# ProPrj_M-power_2025-07-02.net
KiCad netlist of a schematic drawn in EasyEDA Pro
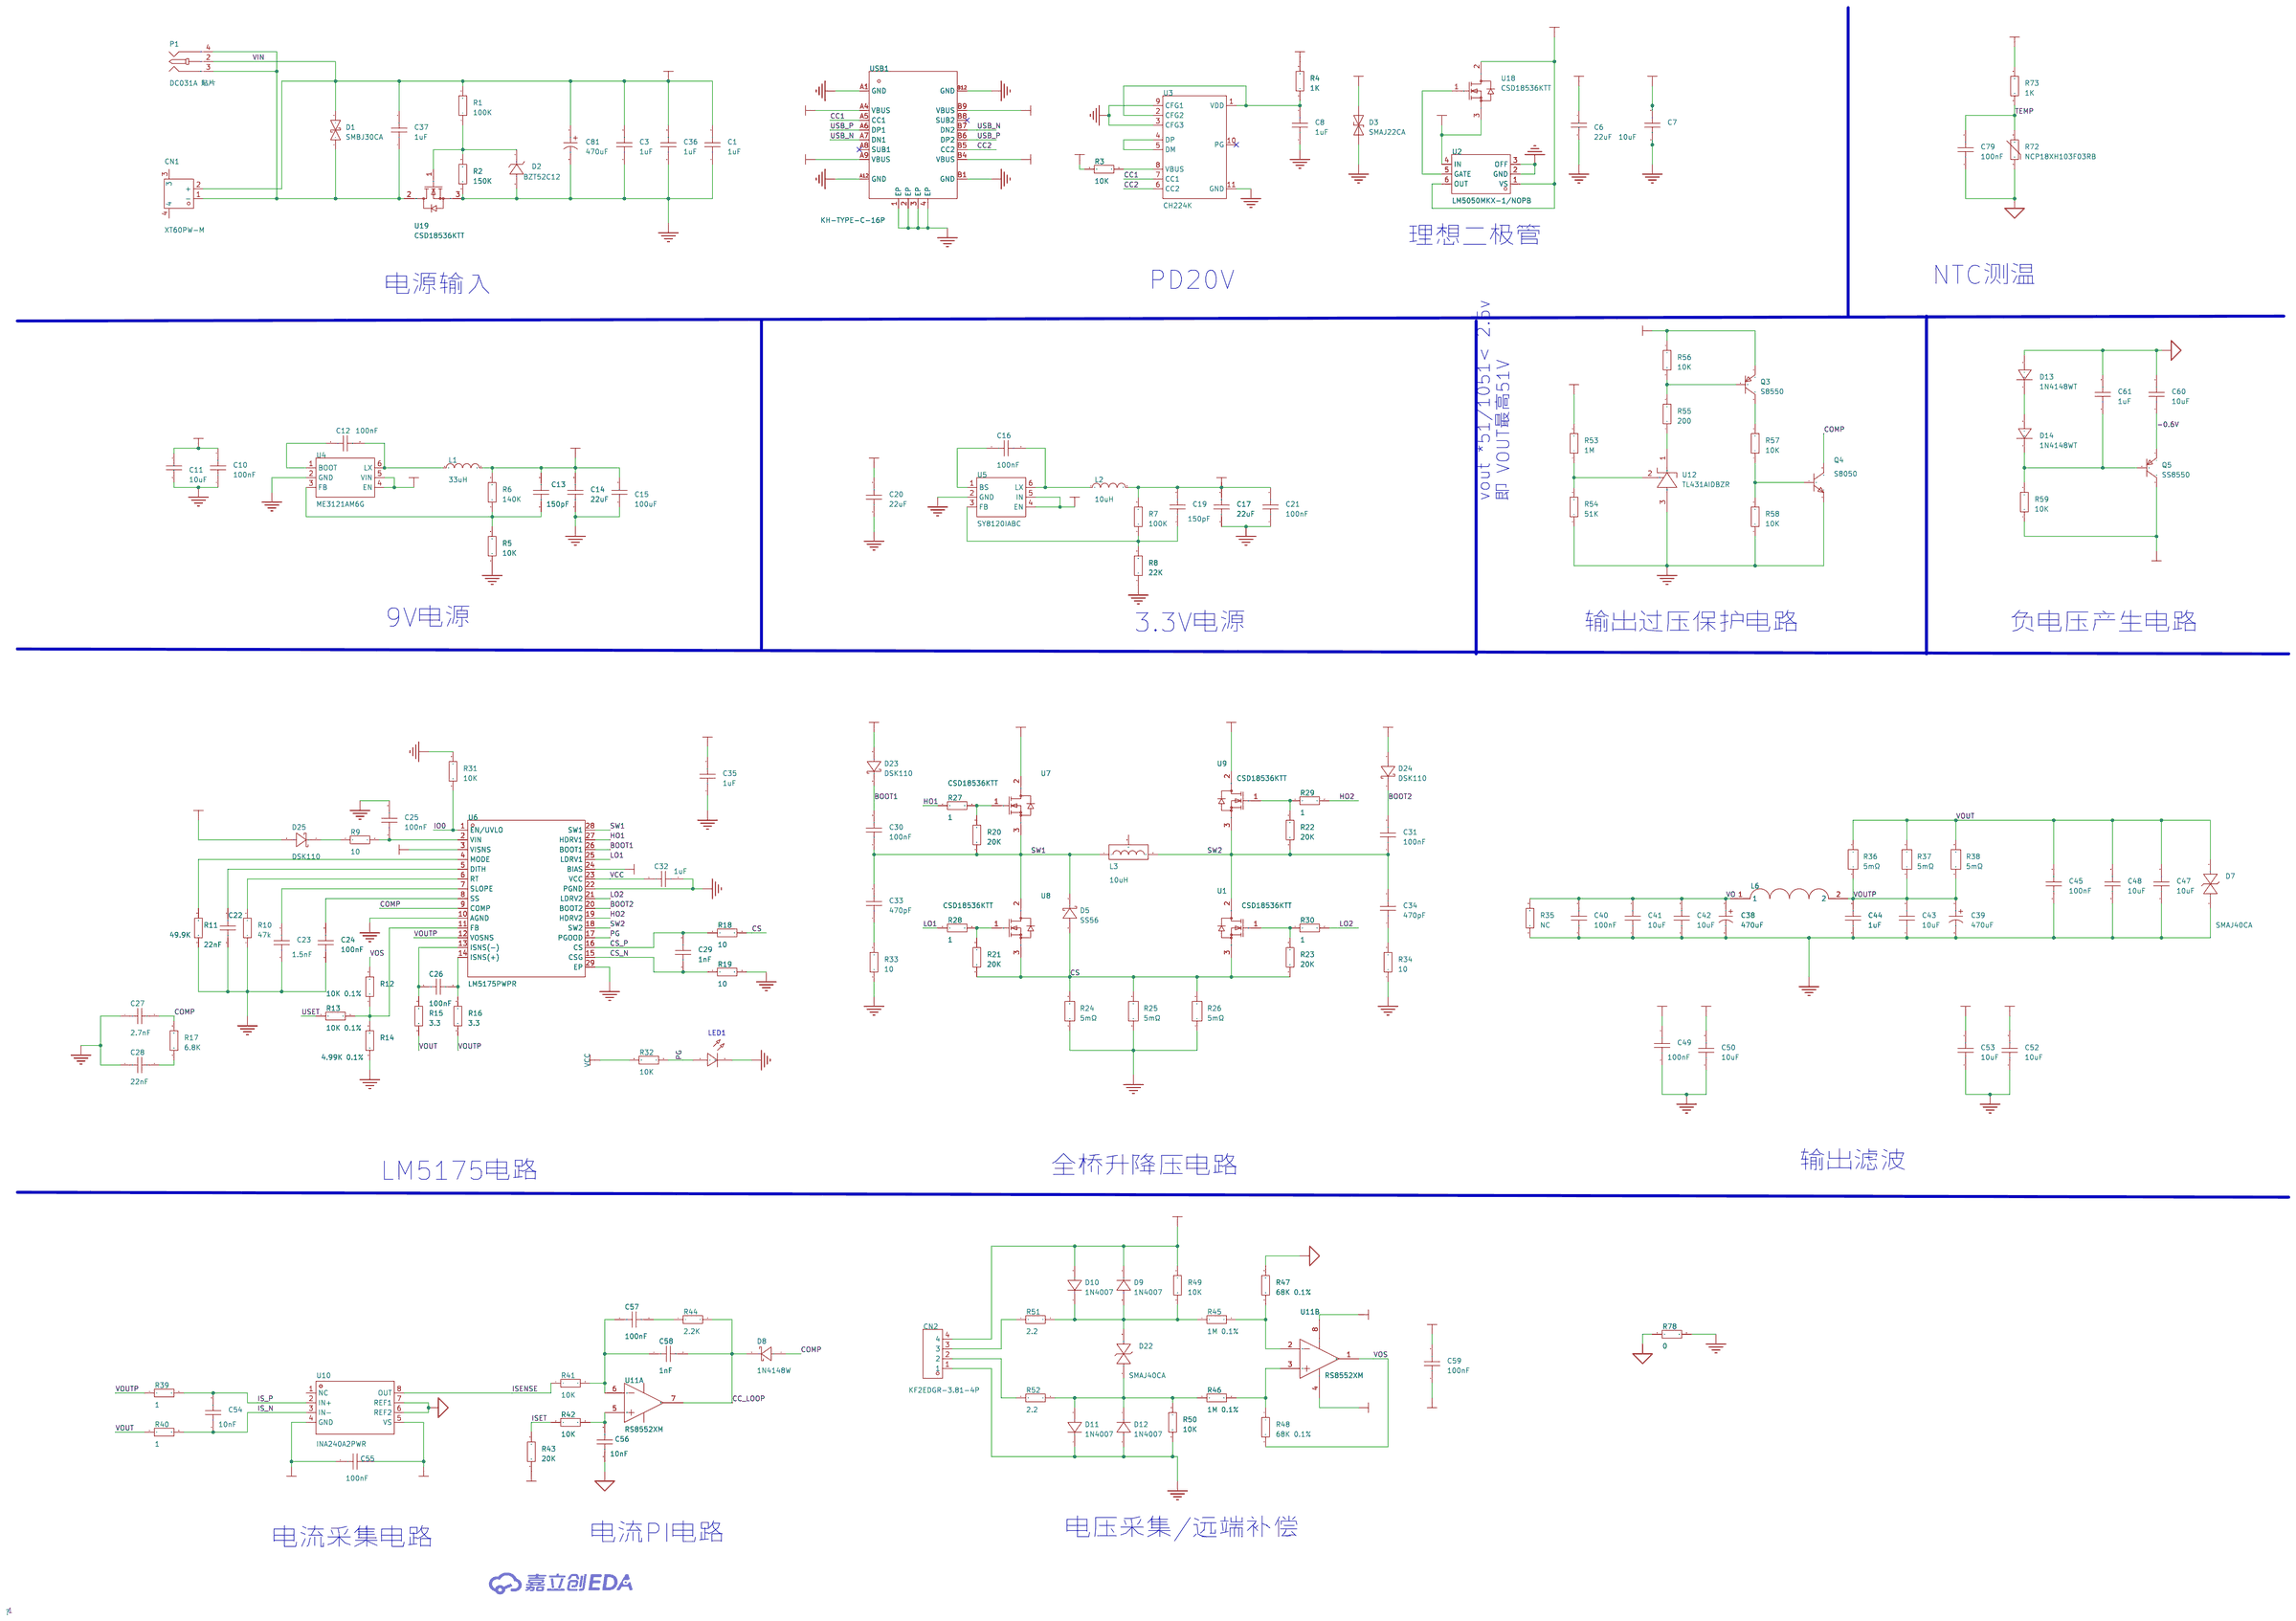
[diagram p0: 功率]
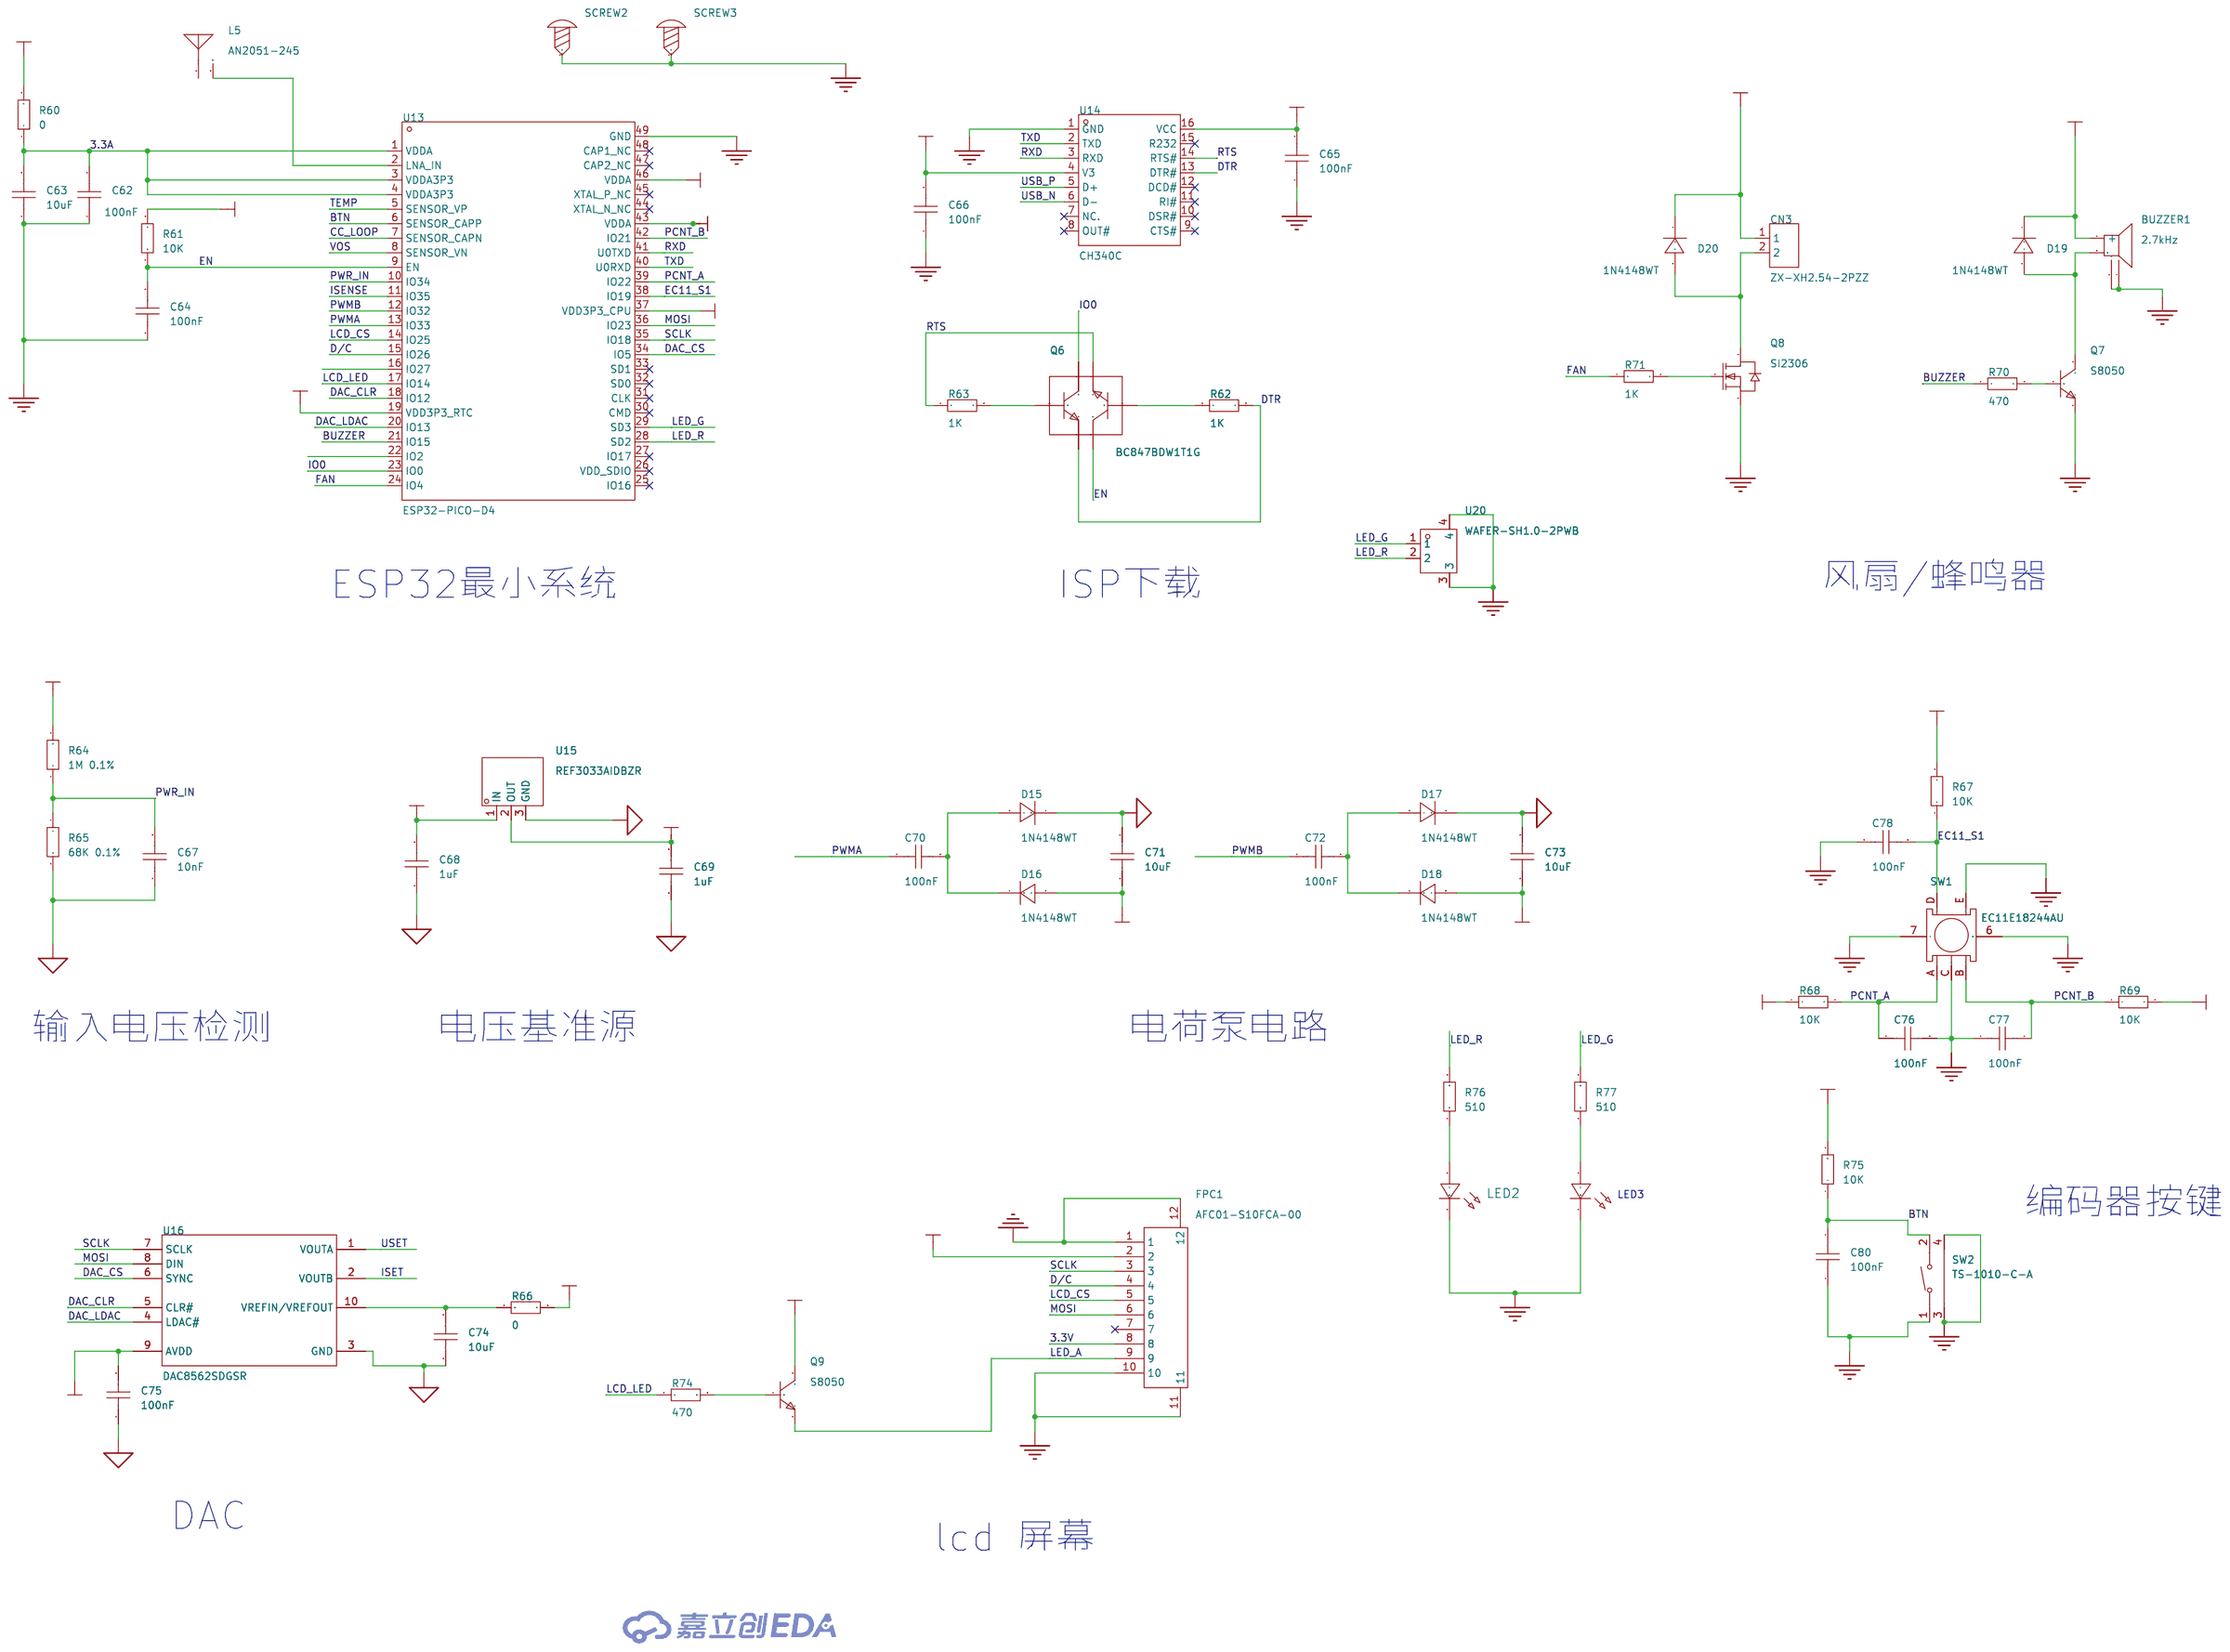
[diagram p1: 控制]

(export (version "E")
  (design (tool "Eeschema 10.0.6"))
  (components
    (comp (ref "C1")
      (value "1uF")
      (footprint "easyedapro:C0603")
      (fields
        (field (name "Manufacturer Part") "CL31B105KBHNNNE")
        (field (name "Manufacturer") "SAMSUNG(三星)")
      )
      (libsource (lib "easyedapro") (part "CapAcitance"))
    )
    (comp (ref "C3")
      (value "1uF")
      (footprint "easyedapro:C0603")
      (fields
        (field (name "Manufacturer Part") "CL31B105KBHNNNE")
        (field (name "Manufacturer") "SAMSUNG(三星)")
      )
      (libsource (lib "easyedapro") (part "CapAcitance"))
    )
    (comp (ref "C6")
      (value "22uF")
      (footprint "easyedapro:C1206")
      (description "容值:22uF;精度:±10%;额定电压:25V;材质(温度系数):X5R;")
      (fields
        (field (name "Manufacturer Part") "CL31A226KAHNNNE")
        (field (name "Manufacturer") "SAMSUNG(三星)")
      )
      (libsource (lib "easyedapro") (part "CL31A226KAHNNNE"))
    )
    (comp (ref "C7")
      (value "10uF")
      (footprint "easyedapro:C0603")
      (description "容值:10uF;精度:±20%;额定电压:25V;材质(温度系数):X5R;")
      (fields
        (field (name "Manufacturer Part") "CL10A106MA8NRNC")
        (field (name "Manufacturer") "SAMSUNG(三星)")
      )
      (libsource (lib "easyedapro") (part "CL10A106MA8NRNC"))
    )
    (comp (ref "C8")
      (value "1uF")
      (footprint "easyedapro:C0603")
      (libsource (lib "easyedapro") (part "CapAcitance"))
    )
    (comp (ref "C10")
      (value "100nF")
      (footprint "easyedapro:C0603")
      (libsource (lib "easyedapro") (part "CapAcitance"))
    )
    (comp (ref "C11")
      (value "10uF")
      (footprint "easyedapro:C1206")
      (description "容值:10uF;精度:±10%;额定电压:50V;材质(温度系数):X5R;")
      (fields
        (field (name "Manufacturer Part") "CL31A106KBHNNNE")
        (field (name "Manufacturer") "SAMSUNG(三星)")
      )
      (libsource (lib "easyedapro") (part "CL31A106KBHNNNE"))
    )
    (comp (ref "C12")
      (value "100nF")
      (footprint "easyedapro:C0603")
      (libsource (lib "easyedapro") (part "CapAcitance"))
    )
    (comp (ref "C13")
      (value "150pF")
      (footprint "easyedapro:C0603")
      (libsource (lib "easyedapro") (part "CapAcitance"))
    )
    (comp (ref "C14")
      (value "22uF")
      (footprint "easyedapro:C0805")
      (description "容值:22uF;精度:±20%;额定电压:25V;材质(温度系数):X5R;")
      (fields
        (field (name "Manufacturer Part") "CL21A226MAYNNNE")
        (field (name "Manufacturer") "SAMSUNG(三星)")
      )
      (libsource (lib "easyedapro") (part "CL21A226MAYNNNE"))
    )
    (comp (ref "C15")
      (value "100uF")
      (footprint "easyedapro:C1206")
      (description "容值:100uF;精度:±20%;额定电压:6.3V;材质(温度系数):X5R;")
      (fields
        (field (name "Manufacturer Part") "CL31A107MQHNNNE")
        (field (name "Manufacturer") "SAMSUNG(三星)")
      )
      (libsource (lib "easyedapro") (part "CL31A107MQHNNNE"))
    )
    (comp (ref "C16")
      (value "100nF")
      (footprint "easyedapro:C0603")
      (libsource (lib "easyedapro") (part "CapAcitance"))
    )
    (comp (ref "C17")
      (value "22uF")
      (footprint "easyedapro:C0603")
      (description "容值:22uF;精度:±20%;额定电压:6.3V;材质(温度系数):X5R;")
      (fields
        (field (name "Manufacturer Part") "CL10A226MQ8NRNC")
        (field (name "Manufacturer") "SAMSUNG(三星)")
      )
      (libsource (lib "easyedapro") (part "CL10A226MQ8NRNC"))
    )
    (comp (ref "C19")
      (value "150pF")
      (footprint "easyedapro:C0603")
      (libsource (lib "easyedapro") (part "CapAcitance"))
    )
    (comp (ref "C20")
      (value "22uF")
      (footprint "easyedapro:C0603")
      (description "容值:22uF;精度:±20%;额定电压:6.3V;材质(温度系数):X5R;")
      (fields
        (field (name "Manufacturer Part") "CL10A226MQ8NRNC")
        (field (name "Manufacturer") "SAMSUNG(三星)")
      )
      (libsource (lib "easyedapro") (part "CL10A226MQ8NRNC"))
    )
    (comp (ref "C21")
      (value "100nF")
      (footprint "easyedapro:C0603")
      (libsource (lib "easyedapro") (part "CapAcitance"))
    )
    (comp (ref "C22")
      (value "22nF")
      (footprint "easyedapro:C0603")
      (libsource (lib "easyedapro") (part "CapAcitance"))
    )
    (comp (ref "C23")
      (value "1.5nF")
      (footprint "easyedapro:C0603")
      (libsource (lib "easyedapro") (part "CapAcitance"))
    )
    (comp (ref "C24")
      (value "100nF")
      (footprint "easyedapro:C0603")
      (libsource (lib "easyedapro") (part "CapAcitance"))
    )
    (comp (ref "C25")
      (value "100nF")
      (footprint "easyedapro:C0603")
      (libsource (lib "easyedapro") (part "CapAcitance"))
    )
    (comp (ref "C26")
      (value "100nF")
      (footprint "easyedapro:C0603")
      (libsource (lib "easyedapro") (part "CapAcitance"))
    )
    (comp (ref "C27")
      (value "2.7nF")
      (footprint "easyedapro:C0603")
      (libsource (lib "easyedapro") (part "CapAcitance"))
    )
    (comp (ref "C28")
      (value "22nF")
      (footprint "easyedapro:C0603")
      (libsource (lib "easyedapro") (part "CapAcitance"))
    )
    (comp (ref "C29")
      (value "1nF")
      (footprint "easyedapro:C0603")
      (libsource (lib "easyedapro") (part "CapAcitance"))
    )
    (comp (ref "C30")
      (value "100nF")
      (footprint "easyedapro:C0603")
      (libsource (lib "easyedapro") (part "CapAcitance"))
    )
    (comp (ref "C31")
      (value "100nF")
      (footprint "easyedapro:C0603")
      (libsource (lib "easyedapro") (part "CapAcitance"))
    )
    (comp (ref "C32")
      (value "1uF")
      (footprint "easyedapro:C0603")
      (libsource (lib "easyedapro") (part "CapAcitance"))
    )
    (comp (ref "C33")
      (value "470pF")
      (footprint "easyedapro:C0603")
      (libsource (lib "easyedapro") (part "CapAcitance"))
    )
    (comp (ref "C34")
      (value "470pF")
      (footprint "easyedapro:C0603")
      (libsource (lib "easyedapro") (part "CapAcitance"))
    )
    (comp (ref "C35")
      (value "1uF")
      (footprint "easyedapro:C0603")
      (libsource (lib "easyedapro") (part "CapAcitance"))
    )
    (comp (ref "C36")
      (value "1uF")
      (footprint "easyedapro:C0603")
      (fields
        (field (name "Manufacturer Part") "CL31B105KBHNNNE")
        (field (name "Manufacturer") "SAMSUNG(三星)")
      )
      (libsource (lib "easyedapro") (part "CapAcitance"))
    )
    (comp (ref "C37")
      (value "1uF")
      (footprint "easyedapro:C0603")
      (fields
        (field (name "Manufacturer Part") "CL31B105KBHNNNE")
        (field (name "Manufacturer") "SAMSUNG(三星)")
      )
      (libsource (lib "easyedapro") (part "CapAcitance"))
    )
    (comp (ref "C38")
      (value "470uF")
      (footprint "easyedapro:CAP-TH_BD10.0-P5.00-D0.6-FD-A")
      (description "容值:470uF;精度:±20%;额定电压:50V;纹波电流:4.1A@100Hz;等效串联电阻(ESR):18mΩ@100kHz;类型:-;")
      (fields (field (name "Manufacturer Part") "PA50V470M10x17") (field (name "Manufacturer") "捷而瑞"))
      (libsource (lib "easyedapro") (part "PA50V470M10X17"))
    )
    (comp (ref "C39")
      (value "470uF")
      (footprint "easyedapro:CAP-TH_BD10.0-P5.00-D0.6-FD-A")
      (description "容值:470uF;精度:±20%;额定电压:50V;纹波电流:4.1A@100Hz;等效串联电阻(ESR):18mΩ@100kHz;类型:-;")
      (fields (field (name "Manufacturer Part") "PA50V470M10x17") (field (name "Manufacturer") "捷而瑞"))
      (libsource (lib "easyedapro") (part "PA50V470M10X17"))
    )
    (comp (ref "C40")
      (value "100nF")
      (footprint "easyedapro:C0603")
      (libsource (lib "easyedapro") (part "CapAcitance"))
    )
    (comp (ref "C41")
      (value "10uF")
      (footprint "easyedapro:C0603")
      (fields
        (field (name "Manufacturer Part") "CL31B105KBHNNNE")
        (field (name "Manufacturer") "SAMSUNG(三星)")
      )
      (libsource (lib "easyedapro") (part "CapAcitance"))
    )
    (comp (ref "C42")
      (value "10uF")
      (footprint "easyedapro:C0603")
      (fields
        (field (name "Manufacturer Part") "CL31B105KBHNNNE")
        (field (name "Manufacturer") "SAMSUNG(三星)")
      )
      (libsource (lib "easyedapro") (part "CapAcitance"))
    )
    (comp (ref "C43")
      (value "10uF")
      (footprint "easyedapro:C0603")
      (fields
        (field (name "Manufacturer Part") "CL31B105KBHNNNE")
        (field (name "Manufacturer") "SAMSUNG(三星)")
      )
      (libsource (lib "easyedapro") (part "CapAcitance"))
    )
    (comp (ref "C44")
      (value "1uF")
      (footprint "easyedapro:C0603")
      (fields
        (field (name "Manufacturer Part") "CL31B105KBHNNNE")
        (field (name "Manufacturer") "SAMSUNG(三星)")
      )
      (libsource (lib "easyedapro") (part "CapAcitance"))
    )
    (comp (ref "C45")
      (value "100nF")
      (footprint "easyedapro:C0603")
      (libsource (lib "easyedapro") (part "CapAcitance"))
    )
    (comp (ref "C47")
      (value "10uF")
      (footprint "easyedapro:C0603")
      (fields
        (field (name "Manufacturer Part") "CL31B105KBHNNNE")
        (field (name "Manufacturer") "SAMSUNG(三星)")
      )
      (libsource (lib "easyedapro") (part "CapAcitance"))
    )
    (comp (ref "C48")
      (value "10uF")
      (footprint "easyedapro:C0603")
      (fields
        (field (name "Manufacturer Part") "CL31B105KBHNNNE")
        (field (name "Manufacturer") "SAMSUNG(三星)")
      )
      (libsource (lib "easyedapro") (part "CapAcitance"))
    )
    (comp (ref "C49")
      (value "100nF")
      (footprint "easyedapro:C0603")
      (libsource (lib "easyedapro") (part "CapAcitance"))
    )
    (comp (ref "C50")
      (value "10uF")
      (footprint "easyedapro:C0603")
      (fields
        (field (name "Manufacturer Part") "CL31B105KBHNNNE")
        (field (name "Manufacturer") "SAMSUNG(三星)")
      )
      (libsource (lib "easyedapro") (part "CapAcitance"))
    )
    (comp (ref "C52")
      (value "10uF")
      (footprint "easyedapro:C0603")
      (fields
        (field (name "Manufacturer Part") "CL31B105KBHNNNE")
        (field (name "Manufacturer") "SAMSUNG(三星)")
      )
      (libsource (lib "easyedapro") (part "CapAcitance"))
    )
    (comp (ref "C53")
      (value "10uF")
      (footprint "easyedapro:C0603")
      (fields
        (field (name "Manufacturer Part") "CL31B105KBHNNNE")
        (field (name "Manufacturer") "SAMSUNG(三星)")
      )
      (libsource (lib "easyedapro") (part "CapAcitance"))
    )
    (comp (ref "C54")
      (value "10nF")
      (footprint "easyedapro:C0603")
      (libsource (lib "easyedapro") (part "CapAcitance"))
    )
    (comp (ref "C55")
      (value "100nF")
      (footprint "easyedapro:C0603")
      (libsource (lib "easyedapro") (part "CapAcitance"))
    )
    (comp (ref "C56")
      (value "10nF")
      (footprint "easyedapro:C0603")
      (libsource (lib "easyedapro") (part "CapAcitance"))
    )
    (comp (ref "C57")
      (value "100nF")
      (footprint "easyedapro:C0603")
      (libsource (lib "easyedapro") (part "CapAcitance"))
    )
    (comp (ref "C58")
      (value "1nF")
      (footprint "easyedapro:C0603")
      (libsource (lib "easyedapro") (part "CapAcitance"))
    )
    (comp (ref "C59")
      (value "100nF")
      (footprint "easyedapro:C0603")
      (libsource (lib "easyedapro") (part "CapAcitance"))
    )
    (comp (ref "C60")
      (value "10uF")
      (footprint "easyedapro:C0603")
      (libsource (lib "easyedapro") (part "CapAcitance"))
    )
    (comp (ref "C61")
      (value "1uF")
      (footprint "easyedapro:C0603")
      (libsource (lib "easyedapro") (part "CapAcitance"))
    )
    (comp (ref "C79")
      (value "100nF")
      (footprint "easyedapro:C0603")
      (libsource (lib "easyedapro") (part "CapAcitance"))
    )
    (comp (ref "C81")
      (value "470uF")
      (footprint "easyedapro:CAP-TH_BD10.0-P5.00-D0.6-FD-A")
      (description "容值:470uF;精度:±20%;额定电压:50V;纹波电流:4.1A@100Hz;等效串联电阻(ESR):18mΩ@100kHz;类型:-;")
      (fields (field (name "Manufacturer Part") "PA50V470M10x17") (field (name "Manufacturer") "捷而瑞"))
      (libsource (lib "easyedapro") (part "PA50V470M10X17"))
    )
    (comp (ref "CN1")
      (value "XT60PW-M")
      (footprint "easyedapro:CONN-TH_XT60PW-M")
      (description "类别:-;类型1:-;")
      (fields (field (name "Manufacturer") "AMASS(艾迈斯)"))
      (libsource (lib "easyedapro") (part "XT60PW-M"))
    )
    (comp (ref "CN2")
      (value "KF2EDGR-3.81-4P")
      (footprint "easyedapro:CONN-TH_4P-P3.81_KF2EDGR-3.81-4P")
      (fields (field (name "Manufacturer") "KEFA(科发)"))
      (libsource (lib "easyedapro") (part "KF2EDGR-3.81-4P"))
    )
    (comp (ref "D1")
      (value "SMBJ30CA")
      (footprint "easyedapro:SMB_L4.6-W3.6-LS5.3-BI")
      (description "反向截止电压(Vrwm):30V;最大钳位电压:48.4V;峰值脉冲电流(Ipp)@10/1000us:12.4A;击穿电压:33.3V;")
      (fields (field (name "Manufacturer") "MDD"))
      (libsource (lib "easyedapro") (part "SMBJ30CA_C113999"))
    )
    (comp (ref "D2")
      (value "BZT52C12")
      (footprint "easyedapro:SOD-123_L2.7-W1.6-LS3.7-RD")
      (description "二极管配置:独立式;稳压值(标称值):12V;稳压值(范围):11.4V~12.6V;功率(Pd):500mW;")
      (fields (field (name "Manufacturer") "宏迦橙"))
      (libsource (lib "easyedapro") (part "BZT52C12_C19077410"))
    )
    (comp (ref "D3")
      (value "SMAJ22CA")
      (footprint "easyedapro:SMA_L4.4-W2.6-LS5.0-BI")
      (description "反向截止电压(Vrwm):22V;最大钳位电压:35.5V;峰值脉冲电流(Ipp):11.3A;峰值脉冲功率(Ppp):400W;击穿电压:24.4V;")
      (fields (field (name "Manufacturer") "Littelfuse(美国力特)"))
      (libsource (lib "easyedapro") (part "SMAJ22CA"))
    )
    (comp (ref "D5")
      (value "SS56")
      (footprint "easyedapro:SMA_L4.3-W2.6-LS5.0-RD")
      (description "二极管配置:独立式;正向压降(Vf):700mV@5.0A;直流反向耐压(Vr):60V;整流电流:5A;")
      (fields (field (name "Manufacturer") "宏迦橙"))
      (libsource (lib "easyedapro") (part "SS56_C18199169"))
    )
    (comp (ref "D7")
      (value "SMAJ40CA")
      (footprint "easyedapro:SMA_L4.3-W2.6-LS5.0-BI")
      (description "极性:双向;反向截止电压(Vrwm):40V;钳位电压:64.5V;峰值脉冲电流(Ipp):6.2A;峰值脉冲功率(Ppp):400W;击穿电压:44.4V;")
      (fields (field (name "Manufacturer") "宏嘉诚"))
      (libsource (lib "easyedapro") (part "SMAJ40CA_C19077552"))
    )
    (comp (ref "D8")
      (value "1N4148W")
      (footprint "easyedapro:SOD-123_L2.7-W1.6-LS3.7-FD")
      (description "二极管配置:独立式;正向压降(Vf):1.25V@150mA;直流反向耐压(Vr):100V;整流电流:150mA;反向恢复时间(trr):4ns;")
      (fields (field (name "Manufacturer") "宏迦橙"))
      (libsource (lib "easyedapro") (part "1N4148W_C7420318"))
    )
    (comp (ref "D9")
      (value "1N4007")
      (footprint "easyedapro:SMA_L4.3-W2.5-LS5.0-RD")
      (description "二极管配置:独立式;正向压降(Vf):1.1V@1A;直流反向耐压(Vr):1kV;整流电流:1A;")
      (fields (field (name "Manufacturer") "TWGMC(台湾迪嘉)"))
      (libsource (lib "easyedapro") (part "1N4007_C727081"))
    )
    (comp (ref "D10")
      (value "1N4007")
      (footprint "easyedapro:SMA_L4.3-W2.5-LS5.0-RD")
      (description "二极管配置:独立式;正向压降(Vf):1.1V@1A;直流反向耐压(Vr):1kV;整流电流:1A;")
      (fields (field (name "Manufacturer") "TWGMC(台湾迪嘉)"))
      (libsource (lib "easyedapro") (part "1N4007_C727081"))
    )
    (comp (ref "D11")
      (value "1N4007")
      (footprint "easyedapro:SMA_L4.3-W2.5-LS5.0-RD")
      (description "二极管配置:独立式;正向压降(Vf):1.1V@1A;直流反向耐压(Vr):1kV;整流电流:1A;")
      (fields (field (name "Manufacturer") "TWGMC(台湾迪嘉)"))
      (libsource (lib "easyedapro") (part "1N4007_C727081"))
    )
    (comp (ref "D12")
      (value "1N4007")
      (footprint "easyedapro:SMA_L4.3-W2.5-LS5.0-RD")
      (description "二极管配置:独立式;正向压降(Vf):1.1V@1A;直流反向耐压(Vr):1kV;整流电流:1A;")
      (fields (field (name "Manufacturer") "TWGMC(台湾迪嘉)"))
      (libsource (lib "easyedapro") (part "1N4007_C727081"))
    )
    (comp (ref "D13")
      (value "1N4148WT")
      (footprint "easyedapro:SOD-523_L1.2-W0.8-LS1.6-RD")
      (description "二极管配置:独立式;正向压降(Vf):1V@10mA;直流反向耐压(Vr):75V;整流电流:300mA;反向恢复时间(trr):4ns;")
      (fields (field (name "Manufacturer") "onsemi(安森美)"))
      (libsource (lib "easyedapro") (part "1N4148WT_C232841"))
    )
    (comp (ref "D14")
      (value "1N4148WT")
      (footprint "easyedapro:SOD-523_L1.2-W0.8-LS1.6-RD")
      (description "二极管配置:独立式;正向压降(Vf):1V@10mA;直流反向耐压(Vr):75V;整流电流:300mA;反向恢复时间(trr):4ns;")
      (fields (field (name "Manufacturer") "onsemi(安森美)"))
      (libsource (lib "easyedapro") (part "1N4148WT_C232841"))
    )
    (comp (ref "D22")
      (value "SMAJ40CA")
      (footprint "easyedapro:SMA_L4.3-W2.6-LS5.0-BI")
      (description "极性:双向;反向截止电压(Vrwm):40V;钳位电压:64.5V;峰值脉冲电流(Ipp):6.2A;峰值脉冲功率(Ppp):400W;击穿电压:44.4V;")
      (fields (field (name "Manufacturer") "宏嘉诚"))
      (libsource (lib "easyedapro") (part "SMAJ40CA_C19077552"))
    )
    (comp (ref "D23")
      (value "DSK110")
      (footprint "easyedapro:SOD-123FL_L2.8-W1.9-LS3.7-RD")
      (description "二极管配置:独立式;正向压降(Vf):850mV@1A;直流反向耐压(Vr):100V;整流电流:1A;")
      (fields (field (name "Manufacturer") "宏迦橙"))
      (libsource (lib "easyedapro") (part "DSK110_C22466354"))
    )
    (comp (ref "D24")
      (value "DSK110")
      (footprint "easyedapro:SOD-123FL_L2.8-W1.9-LS3.7-RD")
      (description "二极管配置:独立式;正向压降(Vf):850mV@1A;直流反向耐压(Vr):100V;整流电流:1A;")
      (fields (field (name "Manufacturer") "宏迦橙"))
      (libsource (lib "easyedapro") (part "DSK110_C22466354"))
    )
    (comp (ref "D25")
      (value "DSK110")
      (footprint "easyedapro:SOD-123FL_L2.8-W1.9-LS3.7-RD")
      (description "二极管配置:独立式;正向压降(Vf):850mV@1A;直流反向耐压(Vr):100V;整流电流:1A;")
      (fields (field (name "Manufacturer") "宏迦橙"))
      (libsource (lib "easyedapro") (part "DSK110_C22466354"))
    )
    (comp (ref "L1")
      (value "33uH")
      (footprint "easyedapro:IND-SMD_L7.0-W6.6_FXL0630")
      (description "电感值:33uH;精度:±20%;额定电流:2A;饱和电流(Isat):2.5A;类型:一体成型电感;")
      (fields (field (name "Manufacturer Part") "FXL0630-330-M") (field (name "Manufacturer") "cjiang(长江微电)"))
      (libsource (lib "easyedapro") (part "FXL0630-330-M"))
    )
    (comp (ref "L2")
      (value "10uH")
      (footprint "easyedapro:IND-SMD_L7.3-W6.8")
      (description "电感值:10uH;精度:±20%;额定电流:4.5A;饱和电流(Isat):5.5A;类型:一体成型电感;")
      (fields (field (name "Manufacturer Part") "FXL0630-100-M") (field (name "Manufacturer") "cjiang(长江微电)"))
      (libsource (lib "easyedapro") (part "FXL0630-100-M"))
    )
    (comp (ref "L3")
      (value "10uH")
      (footprint "easyedapro:IND-SMD_3P-L28.0-W19.4_7443641000B")
      (description "电感值:10uH;精度:±20%;额定电流:30A;饱和电流(Isat):31A;类型:扁平线大电流电感;")
      (fields (field (name "Manufacturer Part") "MTP2918S-100M") (field (name "Manufacturer") "COILMX(迈翔科技)"))
      (libsource (lib "easyedapro") (part "MTP2918S-100M"))
    )
    (comp (ref "L6") (value "~") (libsource (lib "easyedapro") (part "磁棒电感1.5uh")))
    (comp (ref "LED1")
      (value "~")
      (footprint "easyedapro:LED_0603")
      (libsource (lib "easyedapro") (part "LED_G"))
    )
    (comp (ref "P1")
      (value "DC031A 贴片")
      (footprint "easyedapro:DC-IN-SMD_DC031A")
      (description "连接器类型:DC电源插座;安装方式:卧贴;触点内径:1.3mm;触点外径:3.7mm;额定电流:-;额定电压:-;工作温度范围:-;")
      (fields (field (name "Manufacturer") "BOOMELE(博穆精密)"))
      (libsource (lib "easyedapro") (part "DC031A DCseat"))
    )
    (comp (ref "Q3")
      (value "S8550")
      (footprint "easyedapro:SOT-23-3_L2.9-W1.3-P1.90-LS2.4-BR")
      (description "晶体管类型:PNP;集电极电流(Ic):500mA;集射极击穿电压(Vceo):25V;耗散功率(Pd):300mW;直流电流增益(hFE):120@500mA,1.0V;")
      (fields (field (name "Manufacturer") "宏嘉诚"))
      (libsource (lib "easyedapro") (part "S8550_C20069126"))
    )
    (comp (ref "Q4")
      (value "S8050")
      (footprint "easyedapro:SOT-23-3_L2.9-W1.3-P1.90-LS2.3-BR")
      (description "晶体管类型:NPN;集电极电流(Ic):500mA;集射极击穿电压(Vceo):25V;耗散功率(Pd):300mW;直流电流增益(hFE):120@50mA,1.0V;")
      (fields (field (name "Manufacturer") "宏嘉诚"))
      (libsource (lib "easyedapro") (part "S8050_C20069125"))
    )
    (comp (ref "Q5")
      (value "SS8550")
      (footprint "easyedapro:SOT-23-3_L2.9-W1.3-P1.90-LS2.4-BR")
      (description "晶体管类型:PNP;集电极电流(Ic):1.5A;集射极击穿电压(Vceo):25V;耗散功率(Pd):300mW;直流电流增益(hFE):120@100mA,1.0V;")
      (fields (field (name "Manufacturer") "宏嘉诚"))
      (libsource (lib "easyedapro") (part "SS8550_C7420371"))
    )
    (comp (ref "R1") (value "100K") (footprint "easyedapro:R0603") (libsource (lib "easyedapro") (part "电阻")))
    (comp (ref "R2") (value "150K") (footprint "easyedapro:R0603") (libsource (lib "easyedapro") (part "电阻")))
    (comp (ref "R3") (value "10K") (footprint "easyedapro:R0603") (libsource (lib "easyedapro") (part "电阻")))
    (comp (ref "R4") (value "1K") (footprint "easyedapro:R0603") (libsource (lib "easyedapro") (part "电阻")))
    (comp (ref "R5") (value "10K") (footprint "easyedapro:R0603") (libsource (lib "easyedapro") (part "电阻")))
    (comp (ref "R6") (value "140K") (footprint "easyedapro:R0603") (libsource (lib "easyedapro") (part "电阻")))
    (comp (ref "R7") (value "100K") (footprint "easyedapro:R0603") (libsource (lib "easyedapro") (part "电阻")))
    (comp (ref "R8") (value "22K") (footprint "easyedapro:R0603") (libsource (lib "easyedapro") (part "电阻")))
    (comp (ref "R9") (value "10") (footprint "easyedapro:R0603") (libsource (lib "easyedapro") (part "电阻")))
    (comp (ref "R10") (value "47k") (footprint "easyedapro:R0603") (libsource (lib "easyedapro") (part "电阻")))
    (comp (ref "R11")
      (value "49.9K")
      (footprint "easyedapro:R0603")
      (libsource (lib "easyedapro") (part "电阻"))
    )
    (comp (ref "R12")
      (value "10K 0.1%")
      (footprint "easyedapro:R0603")
      (libsource (lib "easyedapro") (part "电阻"))
    )
    (comp (ref "R13")
      (value "10K 0.1%")
      (footprint "easyedapro:R0603")
      (libsource (lib "easyedapro") (part "电阻"))
    )
    (comp (ref "R14")
      (value "4.99K 0.1%")
      (footprint "easyedapro:R0603")
      (libsource (lib "easyedapro") (part "电阻"))
    )
    (comp (ref "R15") (value "3.3") (footprint "easyedapro:R0603") (libsource (lib "easyedapro") (part "电阻")))
    (comp (ref "R16") (value "3.3") (footprint "easyedapro:R0603") (libsource (lib "easyedapro") (part "电阻")))
    (comp (ref "R17")
      (value "6.8K")
      (footprint "easyedapro:R0603")
      (libsource (lib "easyedapro") (part "电阻"))
    )
    (comp (ref "R18") (value "10") (footprint "easyedapro:R0603") (libsource (lib "easyedapro") (part "电阻")))
    (comp (ref "R19") (value "10") (footprint "easyedapro:R0603") (libsource (lib "easyedapro") (part "电阻")))
    (comp (ref "R20") (value "20K") (footprint "easyedapro:R0603") (libsource (lib "easyedapro") (part "电阻")))
    (comp (ref "R21") (value "20K") (footprint "easyedapro:R0603") (libsource (lib "easyedapro") (part "电阻")))
    (comp (ref "R22") (value "20K") (footprint "easyedapro:R0603") (libsource (lib "easyedapro") (part "电阻")))
    (comp (ref "R23") (value "20K") (footprint "easyedapro:R0603") (libsource (lib "easyedapro") (part "电阻")))
    (comp (ref "R24")
      (value "5mΩ")
      (footprint "easyedapro:R2512")
      (description "电阻类型:采样电阻;阻值:5mΩ;精度:±1%;功率:3W;温度系数:±50ppm/°C;")
      (fields (field (name "Manufacturer Part") "JER2512F3R005") (field (name "Manufacturer") "捷而瑞"))
      (libsource (lib "easyedapro") (part "JER2512F3R005"))
    )
    (comp (ref "R25")
      (value "5mΩ")
      (footprint "easyedapro:R2512")
      (description "电阻类型:采样电阻;阻值:5mΩ;精度:±1%;功率:3W;温度系数:±50ppm/°C;")
      (fields (field (name "Manufacturer Part") "JER2512F3R005") (field (name "Manufacturer") "捷而瑞"))
      (libsource (lib "easyedapro") (part "JER2512F3R005"))
    )
    (comp (ref "R26")
      (value "5mΩ")
      (footprint "easyedapro:R2512")
      (description "电阻类型:采样电阻;阻值:5mΩ;精度:±1%;功率:3W;温度系数:±50ppm/°C;")
      (fields (field (name "Manufacturer Part") "JER2512F3R005") (field (name "Manufacturer") "捷而瑞"))
      (libsource (lib "easyedapro") (part "JER2512F3R005"))
    )
    (comp (ref "R27") (value "1") (footprint "easyedapro:R0603") (libsource (lib "easyedapro") (part "电阻")))
    (comp (ref "R28") (value "1") (footprint "easyedapro:R0603") (libsource (lib "easyedapro") (part "电阻")))
    (comp (ref "R29") (value "1") (footprint "easyedapro:R0603") (libsource (lib "easyedapro") (part "电阻")))
    (comp (ref "R30") (value "1") (footprint "easyedapro:R0603") (libsource (lib "easyedapro") (part "电阻")))
    (comp (ref "R31") (value "10K") (footprint "easyedapro:R0603") (libsource (lib "easyedapro") (part "电阻")))
    (comp (ref "R32") (value "10K") (footprint "easyedapro:R0603") (libsource (lib "easyedapro") (part "电阻")))
    (comp (ref "R33") (value "10") (footprint "easyedapro:R0603") (libsource (lib "easyedapro") (part "电阻")))
    (comp (ref "R34") (value "10") (footprint "easyedapro:R0603") (libsource (lib "easyedapro") (part "电阻")))
    (comp (ref "R35") (value "NC") (footprint "easyedapro:R0603") (libsource (lib "easyedapro") (part "电阻")))
    (comp (ref "R36")
      (value "5mΩ")
      (footprint "easyedapro:R2512")
      (description "电阻类型:采样电阻;阻值:5mΩ;精度:±1%;功率:3W;温度系数:±50ppm/°C;")
      (fields (field (name "Manufacturer Part") "JER2512F3R005") (field (name "Manufacturer") "捷而瑞"))
      (libsource (lib "easyedapro") (part "JER2512F3R005"))
    )
    (comp (ref "R37")
      (value "5mΩ")
      (footprint "easyedapro:R2512")
      (description "电阻类型:采样电阻;阻值:5mΩ;精度:±1%;功率:3W;温度系数:±50ppm/°C;")
      (fields (field (name "Manufacturer Part") "JER2512F3R005") (field (name "Manufacturer") "捷而瑞"))
      (libsource (lib "easyedapro") (part "JER2512F3R005"))
    )
    (comp (ref "R38")
      (value "5mΩ")
      (footprint "easyedapro:R2512")
      (description "电阻类型:采样电阻;阻值:5mΩ;精度:±1%;功率:3W;温度系数:±50ppm/°C;")
      (fields (field (name "Manufacturer Part") "JER2512F3R005") (field (name "Manufacturer") "捷而瑞"))
      (libsource (lib "easyedapro") (part "JER2512F3R005"))
    )
    (comp (ref "R39") (value "1") (footprint "easyedapro:R0603") (libsource (lib "easyedapro") (part "电阻")))
    (comp (ref "R40") (value "1") (footprint "easyedapro:R0603") (libsource (lib "easyedapro") (part "电阻")))
    (comp (ref "R41") (value "10K") (footprint "easyedapro:R0603") (libsource (lib "easyedapro") (part "电阻")))
    (comp (ref "R42") (value "10K") (footprint "easyedapro:R0603") (libsource (lib "easyedapro") (part "电阻")))
    (comp (ref "R43") (value "20K") (footprint "easyedapro:R0603") (libsource (lib "easyedapro") (part "电阻")))
    (comp (ref "R44")
      (value "2.2K")
      (footprint "easyedapro:R0603")
      (libsource (lib "easyedapro") (part "电阻"))
    )
    (comp (ref "R45")
      (value "1M 0.1%")
      (footprint "easyedapro:R0603")
      (libsource (lib "easyedapro") (part "电阻"))
    )
    (comp (ref "R46")
      (value "1M 0.1%")
      (footprint "easyedapro:R0603")
      (libsource (lib "easyedapro") (part "电阻"))
    )
    (comp (ref "R47")
      (value "68K 0.1%")
      (footprint "easyedapro:R0603")
      (libsource (lib "easyedapro") (part "电阻"))
    )
    (comp (ref "R48")
      (value "68K 0.1%")
      (footprint "easyedapro:R0603")
      (libsource (lib "easyedapro") (part "电阻"))
    )
    (comp (ref "R49") (value "10K") (footprint "easyedapro:R0603") (libsource (lib "easyedapro") (part "电阻")))
    (comp (ref "R50") (value "10K") (footprint "easyedapro:R0603") (libsource (lib "easyedapro") (part "电阻")))
    (comp (ref "R51") (value "2.2") (footprint "easyedapro:R0603") (libsource (lib "easyedapro") (part "电阻")))
    (comp (ref "R52") (value "2.2") (footprint "easyedapro:R0603") (libsource (lib "easyedapro") (part "电阻")))
    (comp (ref "R53") (value "1M") (footprint "easyedapro:R0603") (libsource (lib "easyedapro") (part "电阻")))
    (comp (ref "R54") (value "51K") (footprint "easyedapro:R0603") (libsource (lib "easyedapro") (part "电阻")))
    (comp (ref "R55") (value "200") (footprint "easyedapro:R0603") (libsource (lib "easyedapro") (part "电阻")))
    (comp (ref "R56") (value "10K") (footprint "easyedapro:R0603") (libsource (lib "easyedapro") (part "电阻")))
    (comp (ref "R57") (value "10K") (footprint "easyedapro:R0603") (libsource (lib "easyedapro") (part "电阻")))
    (comp (ref "R58") (value "10K") (footprint "easyedapro:R0603") (libsource (lib "easyedapro") (part "电阻")))
    (comp (ref "R59") (value "10K") (footprint "easyedapro:R0603") (libsource (lib "easyedapro") (part "电阻")))
    (comp (ref "R72")
      (value "NCP18XH103F03RB")
      (footprint "easyedapro:R0603")
      (description "阻值(25°C):10kΩ;B值(25°C/50°C):3380K;电阻精度:±1%;功率:100mW;B值精度:±1%;最大稳态电流(25°C):310uA;")
      (fields (field (name "Manufacturer") "muRata(村田)"))
      (libsource (lib "easyedapro") (part "NCP18XH103F03RB"))
    )
    (comp (ref "R73") (value "1K") (footprint "easyedapro:R0603") (libsource (lib "easyedapro") (part "电阻")))
    (comp (ref "R78") (value "0") (footprint "easyedapro:R0603") (libsource (lib "easyedapro") (part "电阻")))
    (comp (ref "U1")
      (value "CSD18536KTT")
      (footprint "easyedapro:TO-263-3_L10.4-W10.1-P5.08-LS15.4")
      (fields (field (name "Manufacturer") "TI(德州仪器)"))
      (libsource (lib "easyedapro") (part "CSD18536KTT"))
    )
    (comp (ref "U2")
      (value "LM5050MKX-1/NOPB")
      (footprint "easyedapro:TSOT-23-6_L2.9-W1.6-P0.95-LS2.8-BL")
      (description "LM5050-1 5V 至 75V、400uA IQ ORing FET 控制器")
      (fields (field (name "Manufacturer") "TI(德州仪器)"))
      (libsource (lib "easyedapro") (part "LM5050MKX-1/NOPB"))
    )
    (comp (ref "U3")
      (value "CH224K")
      (footprint "easyedapro:ESSOP-10_L4.9-W3.9-P1.0-LS6.0-TL-EP")
      (fields (field (name "Manufacturer") "WCH(南京沁恒)"))
      (libsource (lib "easyedapro") (part "CH224K"))
    )
    (comp (ref "U4")
      (value "ME3121AM6G")
      (footprint "easyedapro:SOT-23-6_L2.9-W1.6-P0.95-LS2.8-BR")
      (description "功能类型:降压型;输出类型:可调;工作电压:4.7V~40V;输出电压:-;输出电流:-;")
      (fields (field (name "Manufacturer") "MICRONE(南京微盟)"))
      (libsource (lib "easyedapro") (part "ME3121AM6G"))
    )
    (comp (ref "U5")
      (value "SY8120IABC")
      (footprint "easyedapro:SOT-23-6_L2.9-W1.6-P0.95-LS2.8-BL")
      (description "功能类型:降压型;输出类型:-;工作电压:4.2V~18V;输出电压:3.3V;输出电流:2A;")
      (fields (field (name "Manufacturer") "silergy(矽力杰)"))
      (libsource (lib "easyedapro") (part "SY8120IABC"))
    )
    (comp (ref "U6")
      (value "LM5175PWPR")
      (footprint "easyedapro:HTSSOP-28_L9.8-W4.5-P0.65-LS6.6-BL-EP")
      (description "功能类型:升降压型;输出类型:-;工作电压:3.5V~42V;输出电压:-;输出电流:-;")
      (fields (field (name "Manufacturer") "TI(德州仪器)"))
      (libsource (lib "easyedapro") (part "LM5175PWPR"))
    )
    (comp (ref "U7")
      (value "CSD18536KTT")
      (footprint "easyedapro:TO-263-3_L10.4-W10.1-P5.08-LS15.4")
      (fields (field (name "Manufacturer") "TI(德州仪器)"))
      (libsource (lib "easyedapro") (part "CSD18536KTT"))
    )
    (comp (ref "U8")
      (value "CSD18536KTT")
      (footprint "easyedapro:TO-263-3_L10.4-W10.1-P5.08-LS15.4")
      (fields (field (name "Manufacturer") "TI(德州仪器)"))
      (libsource (lib "easyedapro") (part "CSD18536KTT"))
    )
    (comp (ref "U9")
      (value "CSD18536KTT")
      (footprint "easyedapro:TO-263-3_L10.4-W10.1-P5.08-LS15.4")
      (fields (field (name "Manufacturer") "TI(德州仪器)"))
      (libsource (lib "easyedapro") (part "CSD18536KTT"))
    )
    (comp (ref "U10")
      (value "INA240A2PWR")
      (footprint "easyedapro:TSSOP-8_L4.4-W3.0-P0.65-LS6.4-BL")
      (description "放大器数:单路;")
      (fields (field (name "Manufacturer") "TI(德州仪器)"))
      (libsource (lib "easyedapro") (part "INA240A2PWR"))
    )
    (comp (ref "U11")
      (value "RS8552XM")
      (footprint "easyedapro:MSOP-8_L3.0-W3.0-P0.65-LS4.9-BL")
      (description "放大器数:双路;增益带宽积(GBP):4.5MHz;压摆率(SR):2.5V/us;")
      (fields (field (name "Manufacturer") "RUNIC(润石)"))
      (libsource (lib "easyedapro") (part "RS8552XM"))
    )
    (comp (ref "U12")
      (value "TL431AIDBZR")
      (footprint "easyedapro:SOT-23-3_L2.9-W1.6-P1.90-LS2.8-BR")
      (description "输出类型:可调;输入电压:-;输出电压:2.495V~36V;输出电流:100mA;精度:±1%;")
      (fields (field (name "Manufacturer") "TI(德州仪器)"))
      (libsource (lib "easyedapro") (part "TL431AIDBZR"))
    )
    (comp (ref "U18")
      (value "CSD18536KTT")
      (footprint "easyedapro:TO-263-3_L10.4-W10.1-P5.08-LS15.4")
      (fields (field (name "Manufacturer") "TI(德州仪器)"))
      (libsource (lib "easyedapro") (part "CSD18536KTT"))
    )
    (comp (ref "U19")
      (value "CSD18536KTT")
      (footprint "easyedapro:TO-263-3_L10.4-W10.1-P5.08-LS15.4")
      (fields (field (name "Manufacturer") "TI(德州仪器)"))
      (libsource (lib "easyedapro") (part "CSD18536KTT"))
    )
    (comp (ref "USB1")
      (value "KH-TYPE-C-16P")
      (footprint "easyedapro:USB-C-SMD_KH-TYPE-C-16P")
      (description "连接器类型:Type-C;标准:-;公母:母;端口数量:1;触点数量:16P;安装方式:卧贴;额定电流 - 电源:3A;工作温度范围:-40°C~+85°C;")
      (fields (field (name "Manufacturer") "kinghelm(金航标)"))
      (libsource (lib "easyedapro") (part "KH-TYPE-C-16P"))
    )
    (comp (ref "BUZZER1")
      (value "2.7kHz")
      (footprint "easyedapro:BUZ-SMD_4P-L8.5-W8.5-P8.50-BR")
      (description "驱动方式:无源(外部驱动);构造类型:电磁式;频率:2.7kHz;声压(SPL):80dB;")
      (fields (field (name "Manufacturer Part") "MLT-8530") (field (name "Manufacturer") "华能"))
      (libsource (lib "easyedapro") (part "MLT-8530"))
    )
    (comp (ref "C62")
      (value "100nF")
      (footprint "easyedapro:C0603")
      (libsource (lib "easyedapro") (part "CapAcitance"))
    )
    (comp (ref "C63")
      (value "10uF")
      (footprint "easyedapro:C0603")
      (libsource (lib "easyedapro") (part "CapAcitance"))
    )
    (comp (ref "C64")
      (value "100nF")
      (footprint "easyedapro:C0603")
      (libsource (lib "easyedapro") (part "CapAcitance"))
    )
    (comp (ref "C65")
      (value "100nF")
      (footprint "easyedapro:C0603")
      (libsource (lib "easyedapro") (part "CapAcitance"))
    )
    (comp (ref "C66")
      (value "100nF")
      (footprint "easyedapro:C0603")
      (libsource (lib "easyedapro") (part "CapAcitance"))
    )
    (comp (ref "C67")
      (value "10nF")
      (footprint "easyedapro:C0603")
      (libsource (lib "easyedapro") (part "CapAcitance"))
    )
    (comp (ref "C68")
      (value "1uF")
      (footprint "easyedapro:C0603")
      (libsource (lib "easyedapro") (part "CapAcitance"))
    )
    (comp (ref "C69")
      (value "1uF")
      (footprint "easyedapro:C0603")
      (libsource (lib "easyedapro") (part "CapAcitance"))
    )
    (comp (ref "C70")
      (value "100nF")
      (footprint "easyedapro:C0603")
      (libsource (lib "easyedapro") (part "CapAcitance"))
    )
    (comp (ref "C71")
      (value "10uF")
      (footprint "easyedapro:C0603")
      (libsource (lib "easyedapro") (part "CapAcitance"))
    )
    (comp (ref "C72")
      (value "100nF")
      (footprint "easyedapro:C0603")
      (libsource (lib "easyedapro") (part "CapAcitance"))
    )
    (comp (ref "C73")
      (value "10uF")
      (footprint "easyedapro:C0603")
      (libsource (lib "easyedapro") (part "CapAcitance"))
    )
    (comp (ref "C74")
      (value "10uF")
      (footprint "easyedapro:C0603")
      (libsource (lib "easyedapro") (part "CapAcitance"))
    )
    (comp (ref "C75")
      (value "100nF")
      (footprint "easyedapro:C0603")
      (libsource (lib "easyedapro") (part "CapAcitance"))
    )
    (comp (ref "C76")
      (value "100nF")
      (footprint "easyedapro:C0603")
      (libsource (lib "easyedapro") (part "CapAcitance"))
    )
    (comp (ref "C77")
      (value "100nF")
      (footprint "easyedapro:C0603")
      (libsource (lib "easyedapro") (part "CapAcitance"))
    )
    (comp (ref "C78")
      (value "100nF")
      (footprint "easyedapro:C0603")
      (libsource (lib "easyedapro") (part "CapAcitance"))
    )
    (comp (ref "C80")
      (value "100nF")
      (footprint "easyedapro:C0603")
      (libsource (lib "easyedapro") (part "CapAcitance"))
    )
    (comp (ref "CN3")
      (value "ZX-XH2.54-2PZZ")
      (footprint "easyedapro:CONN-TH_2P-P2.50_HX25003-2A")
      (fields (field (name "Manufacturer") "Megastar(兆星)"))
      (libsource (lib "easyedapro") (part "ZX-XH2.54-2PZZ"))
    )
    (comp (ref "D15")
      (value "1N4148WT")
      (footprint "easyedapro:SOD-523_L1.2-W0.8-LS1.6-RD")
      (description "二极管配置:独立式;正向压降(Vf):1V@10mA;直流反向耐压(Vr):75V;整流电流:300mA;反向恢复时间(trr):4ns;")
      (fields (field (name "Manufacturer") "onsemi(安森美)"))
      (libsource (lib "easyedapro") (part "1N4148WT_C232841"))
    )
    (comp (ref "D16")
      (value "1N4148WT")
      (footprint "easyedapro:SOD-523_L1.2-W0.8-LS1.6-RD")
      (description "二极管配置:独立式;正向压降(Vf):1V@10mA;直流反向耐压(Vr):75V;整流电流:300mA;反向恢复时间(trr):4ns;")
      (fields (field (name "Manufacturer") "onsemi(安森美)"))
      (libsource (lib "easyedapro") (part "1N4148WT_C232841"))
    )
    (comp (ref "D17")
      (value "1N4148WT")
      (footprint "easyedapro:SOD-523_L1.2-W0.8-LS1.6-RD")
      (description "二极管配置:独立式;正向压降(Vf):1V@10mA;直流反向耐压(Vr):75V;整流电流:300mA;反向恢复时间(trr):4ns;")
      (fields (field (name "Manufacturer") "onsemi(安森美)"))
      (libsource (lib "easyedapro") (part "1N4148WT_C232841"))
    )
    (comp (ref "D18")
      (value "1N4148WT")
      (footprint "easyedapro:SOD-523_L1.2-W0.8-LS1.6-RD")
      (description "二极管配置:独立式;正向压降(Vf):1V@10mA;直流反向耐压(Vr):75V;整流电流:300mA;反向恢复时间(trr):4ns;")
      (fields (field (name "Manufacturer") "onsemi(安森美)"))
      (libsource (lib "easyedapro") (part "1N4148WT_C232841"))
    )
    (comp (ref "D19")
      (value "1N4148WT")
      (footprint "easyedapro:SOD-523_L1.2-W0.8-LS1.6-RD")
      (description "二极管配置:独立式;正向压降(Vf):1V@10mA;直流反向耐压(Vr):75V;整流电流:300mA;反向恢复时间(trr):4ns;")
      (fields (field (name "Manufacturer") "onsemi(安森美)"))
      (libsource (lib "easyedapro") (part "1N4148WT_C232841"))
    )
    (comp (ref "D20")
      (value "1N4148WT")
      (footprint "easyedapro:SOD-523_L1.2-W0.8-LS1.6-RD")
      (description "二极管配置:独立式;正向压降(Vf):1V@10mA;直流反向耐压(Vr):75V;整流电流:300mA;反向恢复时间(trr):4ns;")
      (fields (field (name "Manufacturer") "onsemi(安森美)"))
      (libsource (lib "easyedapro") (part "1N4148WT_C232841"))
    )
    (comp (ref "FPC1")
      (value "AFC01-S10FCA-00")
      (footprint "easyedapro:FPC-SMD_P0.5-10P_FGS-XJ-H2.0")
      (description "锁定特性:翻盖式;触点类型:下接;触点数量:10P;间距:0.5mm;安装类型:卧贴;")
      (fields (field (name "Manufacturer") "JS(钜硕电子)"))
      (libsource (lib "easyedapro") (part "AFC01-S10FCA-00"))
    )
    (comp (ref "L5")
      (value "AN2051-245")
      (footprint "easyedapro:ANT2051")
      (description "小体积，高增益，WIFI，蓝牙，zigBee 2.4G天线")
      (fields (field (name "Manufacturer") "rainsun(霖昱微)"))
      (libsource (lib "easyedapro") (part "AN2051-245"))
    )
    (comp (ref "LED2")
      (value "~")
      (footprint "easyedapro:LED_0603")
      (libsource (lib "easyedapro") (part "LED_R"))
    )
    (comp (ref "LED3")
      (value "~")
      (footprint "easyedapro:LED_0603")
      (libsource (lib "easyedapro") (part "LED_G"))
    )
    (comp (ref "Q6")
      (value "BC847BDW1T1G")
      (footprint "easyedapro:SOT-363_L2.0-W1.3-P0.65-LS2.1-TL")
      (description "晶体管类型:NPN;集电极电流(Ic):100mA;集射极击穿电压(Vceo):45V;功率(Pd):380mW;直流电流增益(hFE@Ic,Vce):150@10uA,5.0V;")
      (fields (field (name "Manufacturer") "onsemi(安森美)"))
      (libsource (lib "easyedapro") (part "BC847BDW1T1G"))
    )
    (comp (ref "Q7")
      (value "S8050")
      (footprint "easyedapro:SOT-23-3_L2.9-W1.3-P1.90-LS2.3-BR")
      (description "晶体管类型:NPN;集电极电流(Ic):500mA;集射极击穿电压(Vceo):25V;耗散功率(Pd):300mW;直流电流增益(hFE):120@50mA,1.0V;")
      (fields (field (name "Manufacturer") "宏嘉诚"))
      (libsource (lib "easyedapro") (part "S8050_C20069125"))
    )
    (comp (ref "Q8")
      (value "SI2306")
      (footprint "easyedapro:SOT-23-3_L2.9-W1.4-P1.91-LS2.6-BR")
      (fields (field (name "Manufacturer") "TWGMC(台湾迪嘉)"))
      (libsource (lib "easyedapro") (part "SI2306_C727154"))
    )
    (comp (ref "Q9")
      (value "S8050")
      (footprint "easyedapro:SOT-23-3_L2.9-W1.3-P1.90-LS2.3-BR")
      (description "晶体管类型:NPN;集电极电流(Ic):500mA;集射极击穿电压(Vceo):25V;耗散功率(Pd):300mW;直流电流增益(hFE):120@50mA,1.0V;")
      (fields (field (name "Manufacturer") "宏嘉诚"))
      (libsource (lib "easyedapro") (part "S8050_C20069125"))
    )
    (comp (ref "R60") (value "0") (footprint "easyedapro:R0603") (libsource (lib "easyedapro") (part "电阻")))
    (comp (ref "R61") (value "10K") (footprint "easyedapro:R0603") (libsource (lib "easyedapro") (part "电阻")))
    (comp (ref "R62") (value "1K") (footprint "easyedapro:R0603") (libsource (lib "easyedapro") (part "电阻")))
    (comp (ref "R63") (value "1K") (footprint "easyedapro:R0603") (libsource (lib "easyedapro") (part "电阻")))
    (comp (ref "R64")
      (value "1M 0.1%")
      (footprint "easyedapro:R0603")
      (libsource (lib "easyedapro") (part "电阻"))
    )
    (comp (ref "R65")
      (value "68K 0.1%")
      (footprint "easyedapro:R0603")
      (libsource (lib "easyedapro") (part "电阻"))
    )
    (comp (ref "R66") (value "0") (footprint "easyedapro:R0603") (libsource (lib "easyedapro") (part "电阻")))
    (comp (ref "R67") (value "10K") (footprint "easyedapro:R0603") (libsource (lib "easyedapro") (part "电阻")))
    (comp (ref "R68") (value "10K") (footprint "easyedapro:R0603") (libsource (lib "easyedapro") (part "电阻")))
    (comp (ref "R69") (value "10K") (footprint "easyedapro:R0603") (libsource (lib "easyedapro") (part "电阻")))
    (comp (ref "R70") (value "470") (footprint "easyedapro:R0603") (libsource (lib "easyedapro") (part "电阻")))
    (comp (ref "R71") (value "1K") (footprint "easyedapro:R0603") (libsource (lib "easyedapro") (part "电阻")))
    (comp (ref "R74") (value "470") (footprint "easyedapro:R0603") (libsource (lib "easyedapro") (part "电阻")))
    (comp (ref "R75") (value "10K") (footprint "easyedapro:R0603") (libsource (lib "easyedapro") (part "电阻")))
    (comp (ref "R76") (value "510") (footprint "easyedapro:R0603") (libsource (lib "easyedapro") (part "电阻")))
    (comp (ref "R77") (value "510") (footprint "easyedapro:R0603") (libsource (lib "easyedapro") (part "电阻")))
    (comp (ref "SCREW2")
      (value "~")
      (footprint "easyedapro:M3螺丝")
      (libsource (lib "easyedapro") (part "螺丝孔"))
    )
    (comp (ref "SCREW3")
      (value "~")
      (footprint "easyedapro:M3螺丝")
      (libsource (lib "easyedapro") (part "螺丝孔"))
    )
    (comp (ref "SW1")
      (value "EC11E18244AU")
      (footprint "easyedapro:SW-TH_EC11XXXXXXXX")
      (fields (field (name "Manufacturer") "ALPSALPINE(阿尔卑斯阿尔派)"))
      (libsource (lib "easyedapro") (part "EC11E18244AU"))
    )
    (comp (ref "SW2")
      (value "TS-1010-C-A")
      (footprint "easyedapro:KEY-SMD_TX-1010-X-X")
      (fields (field (name "Manufacturer") "XKB Connectivity(中国星坤)"))
      (libsource (lib "easyedapro") (part "TS-1010-C-A"))
    )
    (comp (ref "U13")
      (value "ESP32-PICO-D4")
      (footprint "easyedapro:LGA-48_L7.0-W7.0-P0.50-BL-EP5.4")
      (description "频率范围:2.412GHz~2.484GHz;接口:I2C,SPI;应用领域:IoT；WiFi；蓝牙;数据速率:150Mbps;灵敏度:-97dBm;典型应用频率:2.4GHz;")
      (fields (field (name "Manufacturer") "ESPRESSIF(乐鑫)"))
      (libsource (lib "easyedapro") (part "ESP32-PICO-D4"))
    )
    (comp (ref "U14")
      (value "CH340C")
      (footprint "easyedapro:SOP-16_L10.0-W3.9-P1.27-LS6.0-BL")
      (description "应用功能:收发器;接口协议:USB 2.0;数据速率:2Mbps;")
      (fields (field (name "Manufacturer") "WCH(南京沁恒)"))
      (libsource (lib "easyedapro") (part "CH340C"))
    )
    (comp (ref "U15")
      (value "REF3033AIDBZR")
      (footprint "easyedapro:SOT-23-3_L3.0-W1.7-P0.95-LS2.9-BR")
      (description "输出类型:固定;输入电压:3.35V~5.5V;输出电压:3.3V;输出电流:25mA;精度:±0.2%;")
      (fields (field (name "Manufacturer") "TI(德州仪器)"))
      (libsource (lib "easyedapro") (part "REF3033AIDBZR"))
    )
    (comp (ref "U16")
      (value "DAC8562SDGSR")
      (footprint "easyedapro:VSSOP-10_L3.0-W3.0-P0.50-LS4.9-BL")
      (description "DAC8562 具有 2.5V、4ppm/°C 基准的 16 位、双通道、低功耗、超低毛刺脉冲、电压输出 DAC")
      (fields (field (name "Manufacturer") "TI(德州仪器)"))
      (libsource (lib "easyedapro") (part "DAC8562SDGSR"))
    )
    (comp (ref "U20")
      (value "WAFER-SH1.0-2PWB")
      (footprint "easyedapro:CONN-SMD_2P-P1.00_XUNPU_WAFER-SH1.0-2PWB")
      (fields (field (name "Manufacturer") "XUNPU(讯普)"))
      (libsource (lib "easyedapro") (part "WAFER-SH1.0-2PWB"))
    )
  )
  (nets
    (net (code "1") (name "-0.6V") (class "Default")
      (node (ref "C55") (pin "1") (pinfunction "1_1") (pintype "input"))
      (node (ref "C59") (pin "1") (pinfunction "1_1") (pintype "input"))
      (node (ref "C60") (pin "1") (pinfunction "1_1") (pintype "input"))
      (node (ref "Q5") (pin "2") (pinfunction "E_2") (pintype "unspecified"))
      (node (ref "R43") (pin "1") (pinfunction "1_1") (pintype "input"))
      (node (ref "U10") (pin "4") (pinfunction "GND_4") (pintype "unspecified"))
      (node (ref "U11") (pin "4") (pinfunction "V-_4") (pintype "unspecified"))
    )
    (net (code "2") (name "-2V") (class "Default")
      (node (ref "C71") (pin "1") (pinfunction "1_1") (pintype "input"))
      (node (ref "C73") (pin "1") (pinfunction "1_1") (pintype "input"))
      (node (ref "D16") (pin "2") (pinfunction "A_2") (pintype "unspecified"))
      (node (ref "D18") (pin "2") (pinfunction "A_2") (pintype "unspecified"))
      (node (ref "Q5") (pin "3") (pinfunction "C_3") (pintype "unspecified"))
      (node (ref "R59") (pin "1") (pinfunction "1_1") (pintype "input"))
    )
    (net (code "3") (name "3.3A") (class "Default")
      (node (ref "C62") (pin "2") (pinfunction "2_2") (pintype "input"))
      (node (ref "C63") (pin "2") (pinfunction "2_2") (pintype "input"))
      (node (ref "R60") (pin "1") (pinfunction "1_1") (pintype "input"))
      (node (ref "U13") (pin "1") (pinfunction "VDDA_1") (pintype "unspecified"))
      (node (ref "U13") (pin "19") (pinfunction "VDD3P3_RTC_19") (pintype "unspecified"))
      (node (ref "U13") (pin "3") (pinfunction "VDDA3P3_3") (pintype "unspecified"))
      (node (ref "U13") (pin "37") (pinfunction "VDD3P3_CPU_37") (pintype "unspecified"))
      (node (ref "U13") (pin "4") (pinfunction "VDDA3P3_4") (pintype "unspecified"))
      (node (ref "U13") (pin "43") (pinfunction "VDDA_43") (pintype "unspecified"))
      (node (ref "U13") (pin "46") (pinfunction "VDDA_46") (pintype "unspecified"))
    )
    (net (code "4") (name "3.3V") (class "Default")
      (node (ref "BUZZER1") (pin "1") (pinfunction "+_1") (pintype "unspecified"))
      (node (ref "C17") (pin "2") (pinfunction "2_2") (pintype "unspecified"))
      (node (ref "C19") (pin "2") (pinfunction "2_2") (pintype "input"))
      (node (ref "C21") (pin "2") (pinfunction "2_2") (pintype "input"))
      (node (ref "C55") (pin "2") (pinfunction "2_2") (pintype "input"))
      (node (ref "C59") (pin "2") (pinfunction "2_2") (pintype "input"))
      (node (ref "C65") (pin "2") (pinfunction "2_2") (pintype "input"))
      (node (ref "C66") (pin "2") (pinfunction "2_2") (pintype "input"))
      (node (ref "C68") (pin "2") (pinfunction "2_2") (pintype "input"))
      (node (ref "C75") (pin "2") (pinfunction "2_2") (pintype "input"))
      (node (ref "D19") (pin "1") (pinfunction "C_1") (pintype "unspecified"))
      (node (ref "FPC1") (pin "2") (pinfunction "2_2") (pintype "unspecified"))
      (node (ref "FPC1") (pin "8") (pinfunction "8_8") (pintype "unspecified"))
      (node (ref "L2") (pin "2") (pinfunction "2_2") (pintype "unspecified"))
      (node (ref "Q3") (pin "2") (pinfunction "E_2") (pintype "input"))
      (node (ref "Q9") (pin "3") (pinfunction "C_3") (pintype "input"))
      (node (ref "R56") (pin "1") (pinfunction "1_1") (pintype "input"))
      (node (ref "R60") (pin "2") (pinfunction "2_2") (pintype "input"))
      (node (ref "R61") (pin "2") (pinfunction "2_2") (pintype "input"))
      (node (ref "R67") (pin "2") (pinfunction "2_2") (pintype "input"))
      (node (ref "R68") (pin "1") (pinfunction "1_1") (pintype "input"))
      (node (ref "R69") (pin "2") (pinfunction "2_2") (pintype "input"))
      (node (ref "R7") (pin "2") (pinfunction "2_2") (pintype "input"))
      (node (ref "R73") (pin "2") (pinfunction "2_2") (pintype "input"))
      (node (ref "R75") (pin "2") (pinfunction "2_2") (pintype "input"))
      (node (ref "U10") (pin "5") (pinfunction "VS_5") (pintype "unspecified"))
      (node (ref "U11") (pin "8") (pinfunction "V+_8") (pintype "unspecified"))
      (node (ref "U14") (pin "16") (pinfunction "VCC_16") (pintype "unspecified"))
      (node (ref "U14") (pin "4") (pinfunction "V3_4") (pintype "unspecified"))
      (node (ref "U15") (pin "1") (pinfunction "IN_1") (pintype "unspecified"))
      (node (ref "U16") (pin "9") (pinfunction "AVDD_9") (pintype "unspecified"))
    )
    (net (code "5") (name "9V") (class "Default")
      (node (ref "C13") (pin "2") (pinfunction "2_2") (pintype "input"))
      (node (ref "C14") (pin "2") (pinfunction "2_2") (pintype "unspecified"))
      (node (ref "C15") (pin "2") (pinfunction "2_2") (pintype "input"))
      (node (ref "C20") (pin "2") (pinfunction "2_2") (pintype "unspecified"))
      (node (ref "C35") (pin "2") (pinfunction "2_2") (pintype "input"))
      (node (ref "CN3") (pin "1") (pinfunction "1_1") (pintype "unspecified"))
      (node (ref "D20") (pin "1") (pinfunction "C_1") (pintype "unspecified"))
      (node (ref "L1") (pin "2") (pinfunction "2_2") (pintype "unspecified"))
      (node (ref "R6") (pin "2") (pinfunction "2_2") (pintype "input"))
      (node (ref "U5") (pin "4") (pinfunction "EN_4") (pintype "unspecified"))
      (node (ref "U5") (pin "5") (pinfunction "IN_5") (pintype "unspecified"))
      (node (ref "U6") (pin "24") (pinfunction "BIAS_24") (pintype "unspecified"))
    )
    (net (code "6") (name "AGND") (class "Default")
      (node (ref "C56") (pin "1") (pinfunction "1_1") (pintype "input"))
      (node (ref "C60") (pin "2") (pinfunction "2_2") (pintype "input"))
      (node (ref "C61") (pin "2") (pinfunction "2_2") (pintype "input"))
      (node (ref "C67") (pin "1") (pinfunction "1_1") (pintype "input"))
      (node (ref "C68") (pin "1") (pinfunction "1_1") (pintype "input"))
      (node (ref "C69") (pin "1") (pinfunction "1_1") (pintype "input"))
      (node (ref "C71") (pin "2") (pinfunction "2_2") (pintype "input"))
      (node (ref "C73") (pin "2") (pinfunction "2_2") (pintype "input"))
      (node (ref "C74") (pin "1") (pinfunction "1_1") (pintype "input"))
      (node (ref "C75") (pin "1") (pinfunction "1_1") (pintype "input"))
      (node (ref "C79") (pin "1") (pinfunction "1_1") (pintype "input"))
      (node (ref "D13") (pin "2") (pinfunction "A_2") (pintype "unspecified"))
      (node (ref "D15") (pin "1") (pinfunction "C_1") (pintype "unspecified"))
      (node (ref "D17") (pin "1") (pinfunction "C_1") (pintype "unspecified"))
      (node (ref "R47") (pin "2") (pinfunction "2_2") (pintype "input"))
      (node (ref "R65") (pin "2") (pinfunction "2_2") (pintype "input"))
      (node (ref "R72") (pin "1") (pinfunction "1_1") (pintype "input"))
      (node (ref "R78") (pin "1") (pinfunction "1_1") (pintype "input"))
      (node (ref "U10") (pin "6") (pinfunction "REF2_6") (pintype "unspecified"))
      (node (ref "U10") (pin "7") (pinfunction "REF1_7") (pintype "unspecified"))
      (node (ref "U15") (pin "3") (pinfunction "GND_3") (pintype "unspecified"))
      (node (ref "U16") (pin "3") (pinfunction "GND_3") (pintype "unspecified"))
    )
    (net (code "7") (name "BOOT1") (class "Default")
      (node (ref "C30") (pin "2") (pinfunction "2_2") (pintype "input"))
      (node (ref "D23") (pin "1") (pinfunction "K_1") (pintype "unspecified"))
      (node (ref "U6") (pin "26") (pinfunction "BOOT1_26") (pintype "unspecified"))
    )
    (net (code "8") (name "BOOT2") (class "Default")
      (node (ref "C31") (pin "2") (pinfunction "2_2") (pintype "input"))
      (node (ref "D24") (pin "1") (pinfunction "K_1") (pintype "unspecified"))
      (node (ref "U6") (pin "20") (pinfunction "BOOT2_20") (pintype "unspecified"))
    )
    (net (code "9") (name "BTN") (class "Default")
      (node (ref "C80") (pin "2") (pinfunction "2_2") (pintype "input"))
      (node (ref "R75") (pin "1") (pinfunction "1_1") (pintype "input"))
      (node (ref "SW2") (pin "2") (pinfunction "2_2") (pintype "unspecified"))
      (node (ref "U13") (pin "6") (pinfunction "SENSOR_CAPP_6") (pintype "unspecified"))
    )
    (net (code "10") (name "BUZZER") (class "Default")
      (node (ref "R70") (pin "1") (pinfunction "1_1") (pintype "input"))
      (node (ref "U13") (pin "21") (pinfunction "IO15_21") (pintype "unspecified"))
    )
    (net (code "11") (name "CC1") (class "Default")
      (node (ref "U3") (pin "7") (pinfunction "CC1_7") (pintype "unspecified"))
      (node (ref "USB1") (pin "A5") (pinfunction "CC1_A5") (pintype "unspecified"))
    )
    (net (code "12") (name "CC2") (class "Default")
      (node (ref "U3") (pin "6") (pinfunction "CC2_6") (pintype "unspecified"))
      (node (ref "USB1") (pin "B5") (pinfunction "CC2_B5") (pintype "unspecified"))
    )
    (net (code "13") (name "CC_LOOP") (class "Default")
      (node (ref "C58") (pin "2") (pinfunction "2_2") (pintype "input"))
      (node (ref "D8") (pin "2") (pinfunction "K_2") (pintype "unspecified"))
      (node (ref "R44") (pin "2") (pinfunction "2_2") (pintype "input"))
      (node (ref "U11") (pin "7") (pinfunction "OUT_2_7") (pintype "output"))
      (node (ref "U13") (pin "7") (pinfunction "SENSOR_CAPN_7") (pintype "unspecified"))
    )
    (net (code "14") (name "COMP") (class "Default")
      (node (ref "C27") (pin "2") (pinfunction "2_2") (pintype "input"))
      (node (ref "D8") (pin "1") (pinfunction "A_1") (pintype "unspecified"))
      (node (ref "Q4") (pin "3") (pinfunction "C_3") (pintype "input"))
      (node (ref "R17") (pin "2") (pinfunction "2_2") (pintype "input"))
      (node (ref "U6") (pin "9") (pinfunction "COMP_9") (pintype "unspecified"))
    )
    (net (code "15") (name "CS") (class "Default")
      (node (ref "D5") (pin "2") (pinfunction "A_2") (pintype "unspecified"))
      (node (ref "R18") (pin "2") (pinfunction "2_2") (pintype "input"))
      (node (ref "R21") (pin "1") (pinfunction "1_1") (pintype "input"))
      (node (ref "R23") (pin "1") (pinfunction "1_1") (pintype "input"))
      (node (ref "R24") (pin "2") (pinfunction "2_2") (pintype "unspecified"))
      (node (ref "R25") (pin "2") (pinfunction "2_2") (pintype "unspecified"))
      (node (ref "R26") (pin "2") (pinfunction "2_2") (pintype "unspecified"))
      (node (ref "U1") (pin "3") (pinfunction "S_3") (pintype "unspecified"))
      (node (ref "U8") (pin "3") (pinfunction "S_3") (pintype "unspecified"))
    )
    (net (code "16") (name "CS_N") (class "Default")
      (node (ref "C29") (pin "1") (pinfunction "1_1") (pintype "input"))
      (node (ref "R19") (pin "1") (pinfunction "1_1") (pintype "input"))
      (node (ref "U6") (pin "15") (pinfunction "CSG_15") (pintype "unspecified"))
    )
    (net (code "17") (name "CS_P") (class "Default")
      (node (ref "C29") (pin "2") (pinfunction "2_2") (pintype "input"))
      (node (ref "R18") (pin "1") (pinfunction "1_1") (pintype "input"))
      (node (ref "U6") (pin "16") (pinfunction "CS_16") (pintype "unspecified"))
    )
    (net (code "18") (name "DAC_CLR") (class "Default")
      (node (ref "U13") (pin "18") (pinfunction "IO12_18") (pintype "unspecified"))
      (node (ref "U16") (pin "5") (pinfunction "CLR#_5") (pintype "unspecified"))
    )
    (net (code "19") (name "DAC_CS") (class "Default")
      (node (ref "U13") (pin "34") (pinfunction "IO5_34") (pintype "unspecified"))
      (node (ref "U16") (pin "6") (pinfunction "SYNC_6") (pintype "unspecified"))
    )
    (net (code "20") (name "DAC_LDAC") (class "Default")
      (node (ref "U13") (pin "20") (pinfunction "IO13_20") (pintype "unspecified"))
      (node (ref "U16") (pin "4") (pinfunction "LDAC#_4") (pintype "unspecified"))
    )
    (net (code "21") (name "DTR") (class "Default")
      (node (ref "Q6") (pin "4") (pinfunction "E_4") (pintype "unspecified"))
      (node (ref "R62") (pin "2") (pinfunction "2_2") (pintype "input"))
      (node (ref "U14") (pin "13") (pinfunction "DTR#_13") (pintype "unspecified"))
    )
    (net (code "22") (name "D{slash}C") (class "Default")
      (node (ref "FPC1") (pin "4") (pinfunction "4_4") (pintype "unspecified"))
      (node (ref "U13") (pin "15") (pinfunction "IO26_15") (pintype "unspecified"))
    )
    (net (code "23") (name "EC11_S1") (class "Default")
      (node (ref "C78") (pin "2") (pinfunction "2_2") (pintype "input"))
      (node (ref "R67") (pin "1") (pinfunction "1_1") (pintype "input"))
      (node (ref "SW1") (pin "D") (pinfunction "D_D") (pintype "unspecified"))
      (node (ref "U13") (pin "38") (pinfunction "IO19_38") (pintype "unspecified"))
    )
    (net (code "24") (name "EN") (class "Default")
      (node (ref "C64") (pin "2") (pinfunction "2_2") (pintype "input"))
      (node (ref "Q6") (pin "6") (pinfunction "C_6") (pintype "unspecified"))
      (node (ref "R61") (pin "1") (pinfunction "1_1") (pintype "input"))
      (node (ref "U13") (pin "9") (pinfunction "EN_9") (pintype "unspecified"))
    )
    (net (code "25") (name "FAN") (class "Default")
      (node (ref "R71") (pin "1") (pinfunction "1_1") (pintype "input"))
      (node (ref "U13") (pin "24") (pinfunction "IO4_24") (pintype "unspecified"))
    )
    (net (code "26") (name "GND") (class "Default")
      (node (ref "BUZZER1") (pin "3") (pinfunction "3_3") (pintype "unspecified"))
      (node (ref "BUZZER1") (pin "4") (pinfunction "4_4") (pintype "unspecified"))
      (node (ref "C1") (pin "1") (pinfunction "1_1") (pintype "input"))
      (node (ref "C10") (pin "1") (pinfunction "1_1") (pintype "input"))
      (node (ref "C11") (pin "1") (pinfunction "1_1") (pintype "input"))
      (node (ref "C14") (pin "1") (pinfunction "1_1") (pintype "unspecified"))
      (node (ref "C15") (pin "1") (pinfunction "1_1") (pintype "input"))
      (node (ref "C17") (pin "1") (pinfunction "1_1") (pintype "unspecified"))
      (node (ref "C20") (pin "1") (pinfunction "1_1") (pintype "unspecified"))
      (node (ref "C21") (pin "1") (pinfunction "1_1") (pintype "input"))
      (node (ref "C22") (pin "1") (pinfunction "1_1") (pintype "input"))
      (node (ref "C23") (pin "1") (pinfunction "1_1") (pintype "input"))
      (node (ref "C24") (pin "1") (pinfunction "1_1") (pintype "input"))
      (node (ref "C25") (pin "2") (pinfunction "2_2") (pintype "input"))
      (node (ref "C27") (pin "1") (pinfunction "1_1") (pintype "input"))
      (node (ref "C28") (pin "1") (pinfunction "1_1") (pintype "input"))
      (node (ref "C3") (pin "1") (pinfunction "1_1") (pintype "input"))
      (node (ref "C32") (pin "2") (pinfunction "2_2") (pintype "input"))
      (node (ref "C35") (pin "1") (pinfunction "1_1") (pintype "input"))
      (node (ref "C36") (pin "1") (pinfunction "1_1") (pintype "input"))
      (node (ref "C38") (pin "2") (pinfunction "2_2") (pintype "input"))
      (node (ref "C39") (pin "2") (pinfunction "2_2") (pintype "input"))
      (node (ref "C40") (pin "1") (pinfunction "1_1") (pintype "input"))
      (node (ref "C41") (pin "1") (pinfunction "1_1") (pintype "input"))
      (node (ref "C42") (pin "1") (pinfunction "1_1") (pintype "input"))
      (node (ref "C43") (pin "1") (pinfunction "1_1") (pintype "input"))
      (node (ref "C44") (pin "1") (pinfunction "1_1") (pintype "input"))
      (node (ref "C45") (pin "1") (pinfunction "1_1") (pintype "input"))
      (node (ref "C47") (pin "1") (pinfunction "1_1") (pintype "input"))
      (node (ref "C48") (pin "1") (pinfunction "1_1") (pintype "input"))
      (node (ref "C49") (pin "1") (pinfunction "1_1") (pintype "input"))
      (node (ref "C50") (pin "1") (pinfunction "1_1") (pintype "input"))
      (node (ref "C52") (pin "1") (pinfunction "1_1") (pintype "input"))
      (node (ref "C53") (pin "1") (pinfunction "1_1") (pintype "input"))
      (node (ref "C6") (pin "1") (pinfunction "1_1") (pintype "input"))
      (node (ref "C62") (pin "1") (pinfunction "1_1") (pintype "input"))
      (node (ref "C63") (pin "1") (pinfunction "1_1") (pintype "input"))
      (node (ref "C64") (pin "1") (pinfunction "1_1") (pintype "input"))
      (node (ref "C65") (pin "1") (pinfunction "1_1") (pintype "input"))
      (node (ref "C66") (pin "1") (pinfunction "1_1") (pintype "input"))
      (node (ref "C7") (pin "1") (pinfunction "1_1") (pintype "unspecified"))
      (node (ref "C76") (pin "2") (pinfunction "2_2") (pintype "input"))
      (node (ref "C77") (pin "1") (pinfunction "1_1") (pintype "input"))
      (node (ref "C78") (pin "1") (pinfunction "1_1") (pintype "input"))
      (node (ref "C8") (pin "1") (pinfunction "1_1") (pintype "input"))
      (node (ref "C80") (pin "1") (pinfunction "1_1") (pintype "input"))
      (node (ref "C81") (pin "2") (pinfunction "2_2") (pintype "input"))
      (node (ref "CN2") (pin "1") (pinfunction "1_1") (pintype "unspecified"))
      (node (ref "D11") (pin "1") (pinfunction "K_1") (pintype "unspecified"))
      (node (ref "D12") (pin "2") (pinfunction "A_2") (pintype "unspecified"))
      (node (ref "D2") (pin "2") (pinfunction "A_2") (pintype "unspecified"))
      (node (ref "D3") (pin "1") (pinfunction "K_1") (pintype "unspecified"))
      (node (ref "D7") (pin "1") (pinfunction "1_1") (pintype "unspecified"))
      (node (ref "FPC1") (pin "1") (pinfunction "1_1") (pintype "unspecified"))
      (node (ref "FPC1") (pin "10") (pinfunction "10_10") (pintype "unspecified"))
      (node (ref "FPC1") (pin "11") (pinfunction "11_11") (pintype "unspecified"))
      (node (ref "FPC1") (pin "12") (pinfunction "12_12") (pintype "unspecified"))
      (node (ref "LED1") (pin "1") (pinfunction "C_1") (pintype "input"))
      (node (ref "LED2") (pin "1") (pinfunction "C_1") (pintype "input"))
      (node (ref "LED3") (pin "1") (pinfunction "C_1") (pintype "input"))
      (node (ref "Q4") (pin "2") (pinfunction "E_2") (pintype "input"))
      (node (ref "Q7") (pin "2") (pinfunction "E_2") (pintype "input"))
      (node (ref "Q8") (pin "2") (pinfunction "S_2") (pintype "unspecified"))
      (node (ref "R10") (pin "1") (pinfunction "1_1") (pintype "input"))
      (node (ref "R11") (pin "1") (pinfunction "1_1") (pintype "input"))
      (node (ref "R14") (pin "1") (pinfunction "1_1") (pintype "input"))
      (node (ref "R19") (pin "2") (pinfunction "2_2") (pintype "input"))
      (node (ref "R2") (pin "1") (pinfunction "1_1") (pintype "input"))
      (node (ref "R24") (pin "1") (pinfunction "1_1") (pintype "unspecified"))
      (node (ref "R25") (pin "1") (pinfunction "1_1") (pintype "unspecified"))
      (node (ref "R26") (pin "1") (pinfunction "1_1") (pintype "unspecified"))
      (node (ref "R31") (pin "2") (pinfunction "2_2") (pintype "input"))
      (node (ref "R33") (pin "1") (pinfunction "1_1") (pintype "input"))
      (node (ref "R34") (pin "1") (pinfunction "1_1") (pintype "input"))
      (node (ref "R35") (pin "1") (pinfunction "1_1") (pintype "input"))
      (node (ref "R5") (pin "1") (pinfunction "1_1") (pintype "input"))
      (node (ref "R50") (pin "2") (pinfunction "2_2") (pintype "input"))
      (node (ref "R54") (pin "1") (pinfunction "1_1") (pintype "input"))
      (node (ref "R58") (pin "1") (pinfunction "1_1") (pintype "input"))
      (node (ref "R78") (pin "2") (pinfunction "2_2") (pintype "input"))
      (node (ref "R8") (pin "1") (pinfunction "1_1") (pintype "input"))
      (node (ref "SCREW2") (pin "1") (pinfunction "1_1") (pintype "input"))
      (node (ref "SCREW3") (pin "1") (pinfunction "1_1") (pintype "input"))
      (node (ref "SW1") (pin "6") (pinfunction "6_6") (pintype "unspecified"))
      (node (ref "SW1") (pin "7") (pinfunction "7_7") (pintype "unspecified"))
      (node (ref "SW1") (pin "C") (pinfunction "C_C") (pintype "unspecified"))
      (node (ref "SW1") (pin "E") (pinfunction "E_E") (pintype "unspecified"))
      (node (ref "SW2") (pin "1") (pinfunction "1_1") (pintype "unspecified"))
      (node (ref "SW2") (pin "3") (pinfunction "3_3") (pintype "unspecified"))
      (node (ref "SW2") (pin "4") (pinfunction "4_4") (pintype "unspecified"))
      (node (ref "U12") (pin "3") (pinfunction "ANODE_3") (pintype "unspecified"))
      (node (ref "U13") (pin "49") (pinfunction "GND_49") (pintype "unspecified"))
      (node (ref "U14") (pin "1") (pinfunction "GND_1") (pintype "unspecified"))
      (node (ref "U19") (pin "3") (pinfunction "S_3") (pintype "unspecified"))
      (node (ref "U2") (pin "2") (pinfunction "GND_2") (pintype "unspecified"))
      (node (ref "U2") (pin "3") (pinfunction "OFF_3") (pintype "unspecified"))
      (node (ref "U20") (pin "3") (pinfunction "3_3") (pintype "unspecified"))
      (node (ref "U20") (pin "4") (pinfunction "4_4") (pintype "unspecified"))
      (node (ref "U3") (pin "11") (pinfunction "GND_11") (pintype "unspecified"))
      (node (ref "U3") (pin "3") (pinfunction "CFG3_3") (pintype "unspecified"))
      (node (ref "U3") (pin "9") (pinfunction "CFG1_9") (pintype "unspecified"))
      (node (ref "U4") (pin "2") (pinfunction "GND_2") (pintype "unspecified"))
      (node (ref "U5") (pin "2") (pinfunction "GND_2") (pintype "unspecified"))
      (node (ref "U6") (pin "10") (pinfunction "AGND_10") (pintype "unspecified"))
      (node (ref "U6") (pin "22") (pinfunction "PGND_22") (pintype "unspecified"))
      (node (ref "U6") (pin "29") (pinfunction "EP_29") (pintype "unspecified"))
      (node (ref "USB1") (pin "1") (pinfunction "EP_1") (pintype "unspecified"))
      (node (ref "USB1") (pin "2") (pinfunction "EP_2") (pintype "unspecified"))
      (node (ref "USB1") (pin "3") (pinfunction "EP_3") (pintype "unspecified"))
      (node (ref "USB1") (pin "4") (pinfunction "EP_4") (pintype "unspecified"))
      (node (ref "USB1") (pin "A1") (pinfunction "GND_A1") (pintype "unspecified"))
      (node (ref "USB1") (pin "A12") (pinfunction "GND_A12") (pintype "unspecified"))
      (node (ref "USB1") (pin "B1") (pinfunction "GND_B1") (pintype "unspecified"))
      (node (ref "USB1") (pin "B12") (pinfunction "GND_B12") (pintype "unspecified"))
    )
    (net (code "27") (name "HO1") (class "Default")
      (node (ref "R27") (pin "1") (pinfunction "1_1") (pintype "input"))
      (node (ref "U6") (pin "27") (pinfunction "HDRV1_27") (pintype "unspecified"))
    )
    (net (code "28") (name "HO2") (class "Default")
      (node (ref "R29") (pin "2") (pinfunction "2_2") (pintype "input"))
      (node (ref "U6") (pin "19") (pinfunction "HDRV2_19") (pintype "unspecified"))
    )
    (net (code "29") (name "IO0") (class "Default")
      (node (ref "Q6") (pin "3") (pinfunction "C_3") (pintype "unspecified"))
      (node (ref "R31") (pin "1") (pinfunction "1_1") (pintype "input"))
      (node (ref "U13") (pin "23") (pinfunction "IO0_23") (pintype "unspecified"))
      (node (ref "U6") (pin "1") (pinfunction "EN/UVLO_1") (pintype "unspecified"))
    )
    (net (code "30") (name "ISENSE") (class "Default")
      (node (ref "R41") (pin "1") (pinfunction "1_1") (pintype "input"))
      (node (ref "U10") (pin "8") (pinfunction "OUT_8") (pintype "unspecified"))
      (node (ref "U13") (pin "11") (pinfunction "IO35_11") (pintype "unspecified"))
    )
    (net (code "31") (name "ISET") (class "Default")
      (node (ref "R42") (pin "1") (pinfunction "1_1") (pintype "input"))
      (node (ref "R43") (pin "2") (pinfunction "2_2") (pintype "input"))
      (node (ref "U16") (pin "2") (pinfunction "VOUTB_2") (pintype "output"))
    )
    (net (code "32") (name "IS_N") (class "Default")
      (node (ref "C54") (pin "1") (pinfunction "1_1") (pintype "input"))
      (node (ref "R40") (pin "2") (pinfunction "2_2") (pintype "input"))
      (node (ref "U10") (pin "3") (pinfunction "IN-_3") (pintype "unspecified"))
    )
    (net (code "33") (name "IS_P") (class "Default")
      (node (ref "C54") (pin "2") (pinfunction "2_2") (pintype "input"))
      (node (ref "R39") (pin "2") (pinfunction "2_2") (pintype "input"))
      (node (ref "U10") (pin "2") (pinfunction "IN+_2") (pintype "unspecified"))
    )
    (net (code "34") (name "LCD_CS") (class "Default")
      (node (ref "FPC1") (pin "5") (pinfunction "5_5") (pintype "unspecified"))
      (node (ref "U13") (pin "14") (pinfunction "IO25_14") (pintype "unspecified"))
    )
    (net (code "35") (name "LCD_LED") (class "Default")
      (node (ref "R74") (pin "1") (pinfunction "1_1") (pintype "input"))
      (node (ref "U13") (pin "17") (pinfunction "IO14_17") (pintype "unspecified"))
    )
    (net (code "36") (name "LED_A") (class "Default")
      (node (ref "FPC1") (pin "9") (pinfunction "9_9") (pintype "unspecified"))
      (node (ref "Q9") (pin "2") (pinfunction "E_2") (pintype "input"))
    )
    (net (code "37") (name "LED_G") (class "Default")
      (node (ref "R77") (pin "2") (pinfunction "2_2") (pintype "input"))
      (node (ref "U13") (pin "29") (pinfunction "SD3_29") (pintype "unspecified"))
      (node (ref "U20") (pin "1") (pinfunction "1_1") (pintype "unspecified"))
    )
    (net (code "38") (name "LED_R") (class "Default")
      (node (ref "R76") (pin "2") (pinfunction "2_2") (pintype "input"))
      (node (ref "U13") (pin "28") (pinfunction "SD2_28") (pintype "unspecified"))
      (node (ref "U20") (pin "2") (pinfunction "2_2") (pintype "unspecified"))
    )
    (net (code "39") (name "LO1") (class "Default")
      (node (ref "R28") (pin "1") (pinfunction "1_1") (pintype "input"))
      (node (ref "U6") (pin "25") (pinfunction "LDRV1_25") (pintype "unspecified"))
    )
    (net (code "40") (name "LO2") (class "Default")
      (node (ref "R30") (pin "2") (pinfunction "2_2") (pintype "input"))
      (node (ref "U6") (pin "21") (pinfunction "LDRV2_21") (pintype "unspecified"))
    )
    (net (code "41") (name "MOSI") (class "Default")
      (node (ref "FPC1") (pin "6") (pinfunction "6_6") (pintype "unspecified"))
      (node (ref "U13") (pin "36") (pinfunction "IO23_36") (pintype "unspecified"))
      (node (ref "U16") (pin "8") (pinfunction "DIN_8") (pintype "unspecified"))
    )
    (net (code "42") (name "Net-(C28-Pad2)") (class "Default")
      (node (ref "C28") (pin "2") (pinfunction "2_2") (pintype "input"))
      (node (ref "R17") (pin "1") (pinfunction "1_1") (pintype "input"))
    )
    (net (code "43") (name "Net-(C33-Pad1)") (class "Default")
      (node (ref "C33") (pin "1") (pinfunction "1_1") (pintype "input"))
      (node (ref "R33") (pin "2") (pinfunction "2_2") (pintype "input"))
    )
    (net (code "44") (name "Net-(C34-Pad1)") (class "Default")
      (node (ref "C34") (pin "1") (pinfunction "1_1") (pintype "input"))
      (node (ref "R34") (pin "2") (pinfunction "2_2") (pintype "input"))
    )
    (net (code "45") (name "Net-(C57-Pad2)") (class "Default")
      (node (ref "C57") (pin "2") (pinfunction "2_2") (pintype "input"))
      (node (ref "R44") (pin "1") (pinfunction "1_1") (pintype "input"))
    )
    (net (code "46") (name "Net-(CN1--)") (class "Default")
      (node (ref "C37") (pin "1") (pinfunction "1_1") (pintype "input"))
      (node (ref "CN1") (pin "1") (pinfunction "-_1") (pintype "unspecified"))
      (node (ref "D1") (pin "1") (pinfunction "K_1") (pintype "input"))
      (node (ref "P1") (pin "3") (pinfunction "3_3") (pintype "unspecified"))
      (node (ref "P1") (pin "4") (pinfunction "4_4") (pintype "unspecified"))
      (node (ref "U19") (pin "2") (pinfunction "D_2") (pintype "unspecified"))
    )
    (net (code "47") (name "Net-(CN2-Pad2)") (class "Default")
      (node (ref "CN2") (pin "2") (pinfunction "2_2") (pintype "unspecified"))
      (node (ref "R52") (pin "1") (pinfunction "1_1") (pintype "input"))
    )
    (net (code "48") (name "Net-(CN2-Pad3)") (class "Default")
      (node (ref "CN2") (pin "3") (pinfunction "3_3") (pintype "unspecified"))
      (node (ref "R51") (pin "1") (pinfunction "1_1") (pintype "input"))
    )
    (net (code "49") (name "Net-(D2-K)") (class "Default")
      (node (ref "D2") (pin "1") (pinfunction "K_1") (pintype "unspecified"))
      (node (ref "R1") (pin "1") (pinfunction "1_1") (pintype "input"))
      (node (ref "R2") (pin "2") (pinfunction "2_2") (pintype "input"))
      (node (ref "U19") (pin "1") (pinfunction "G_1") (pintype "unspecified"))
    )
    (net (code "50") (name "Net-(D10-K)") (class "Default")
      (node (ref "D10") (pin "1") (pinfunction "K_1") (pintype "unspecified"))
      (node (ref "D22") (pin "2") (pinfunction "2_2") (pintype "unspecified"))
      (node (ref "D9") (pin "2") (pinfunction "A_2") (pintype "unspecified"))
      (node (ref "R45") (pin "1") (pinfunction "1_1") (pintype "input"))
      (node (ref "R49") (pin "2") (pinfunction "2_2") (pintype "input"))
      (node (ref "R51") (pin "2") (pinfunction "2_2") (pintype "input"))
    )
    (net (code "51") (name "Net-(D11-A)") (class "Default")
      (node (ref "D11") (pin "2") (pinfunction "A_2") (pintype "unspecified"))
      (node (ref "D12") (pin "1") (pinfunction "K_1") (pintype "unspecified"))
      (node (ref "D22") (pin "1") (pinfunction "1_1") (pintype "unspecified"))
      (node (ref "R46") (pin "1") (pinfunction "1_1") (pintype "input"))
      (node (ref "R50") (pin "1") (pinfunction "1_1") (pintype "input"))
      (node (ref "R52") (pin "2") (pinfunction "2_2") (pintype "input"))
    )
    (net (code "52") (name "Net-(D13-C)") (class "Default")
      (node (ref "D13") (pin "1") (pinfunction "C_1") (pintype "unspecified"))
      (node (ref "D14") (pin "2") (pinfunction "A_2") (pintype "unspecified"))
    )
    (net (code "53") (name "Net-(D14-C)") (class "Default")
      (node (ref "C61") (pin "1") (pinfunction "1_1") (pintype "input"))
      (node (ref "D14") (pin "1") (pinfunction "C_1") (pintype "unspecified"))
      (node (ref "Q5") (pin "1") (pinfunction "B_1") (pintype "unspecified"))
      (node (ref "R59") (pin "2") (pinfunction "2_2") (pintype "input"))
    )
    (net (code "54") (name "Net-(D15-A)") (class "Default")
      (node (ref "C70") (pin "2") (pinfunction "2_2") (pintype "input"))
      (node (ref "D15") (pin "2") (pinfunction "A_2") (pintype "unspecified"))
      (node (ref "D16") (pin "1") (pinfunction "C_1") (pintype "unspecified"))
    )
    (net (code "55") (name "Net-(D17-A)") (class "Default")
      (node (ref "C72") (pin "2") (pinfunction "2_2") (pintype "input"))
      (node (ref "D17") (pin "2") (pinfunction "A_2") (pintype "unspecified"))
      (node (ref "D18") (pin "1") (pinfunction "C_1") (pintype "unspecified"))
    )
    (net (code "56") (name "Net-(D19-A)") (class "Default")
      (node (ref "BUZZER1") (pin "2") (pinfunction "2_2") (pintype "unspecified"))
      (node (ref "D19") (pin "2") (pinfunction "A_2") (pintype "unspecified"))
      (node (ref "Q7") (pin "3") (pinfunction "C_3") (pintype "input"))
    )
    (net (code "57") (name "Net-(D20-A)") (class "Default")
      (node (ref "CN3") (pin "2") (pinfunction "2_2") (pintype "unspecified"))
      (node (ref "D20") (pin "2") (pinfunction "A_2") (pintype "unspecified"))
      (node (ref "Q8") (pin "3") (pinfunction "D_3") (pintype "unspecified"))
    )
    (net (code "58") (name "Net-(D25-K)") (class "Default")
      (node (ref "D25") (pin "1") (pinfunction "K_1") (pintype "unspecified"))
      (node (ref "R9") (pin "1") (pinfunction "1_1") (pintype "input"))
    )
    (net (code "59") (name "Net-(LED2-A)") (class "Default")
      (node (ref "LED2") (pin "2") (pinfunction "A_2") (pintype "input"))
      (node (ref "R76") (pin "1") (pinfunction "1_1") (pintype "input"))
    )
    (net (code "60") (name "Net-(LED3-A)") (class "Default")
      (node (ref "LED3") (pin "2") (pinfunction "A_2") (pintype "input"))
      (node (ref "R77") (pin "1") (pinfunction "1_1") (pintype "input"))
    )
    (net (code "61") (name "Net-(Q3-B)") (class "Default")
      (node (ref "Q3") (pin "1") (pinfunction "B_1") (pintype "input"))
      (node (ref "R55") (pin "2") (pinfunction "2_2") (pintype "input"))
      (node (ref "R56") (pin "2") (pinfunction "2_2") (pintype "input"))
    )
    (net (code "62") (name "Net-(Q3-C)") (class "Default")
      (node (ref "Q3") (pin "3") (pinfunction "C_3") (pintype "input"))
      (node (ref "R57") (pin "2") (pinfunction "2_2") (pintype "input"))
    )
    (net (code "63") (name "Net-(Q4-B)") (class "Default")
      (node (ref "Q4") (pin "1") (pinfunction "B_1") (pintype "input"))
      (node (ref "R57") (pin "1") (pinfunction "1_1") (pintype "input"))
      (node (ref "R58") (pin "2") (pinfunction "2_2") (pintype "input"))
    )
    (net (code "64") (name "Net-(Q6-B-Pad2)") (class "Default")
      (node (ref "Q6") (pin "2") (pinfunction "B_2") (pintype "unspecified"))
      (node (ref "R62") (pin "1") (pinfunction "1_1") (pintype "input"))
    )
    (net (code "65") (name "Net-(Q6-B-Pad5)") (class "Default")
      (node (ref "Q6") (pin "5") (pinfunction "B_5") (pintype "unspecified"))
      (node (ref "R63") (pin "2") (pinfunction "2_2") (pintype "input"))
    )
    (net (code "66") (name "Net-(Q7-B)") (class "Default")
      (node (ref "Q7") (pin "1") (pinfunction "B_1") (pintype "input"))
      (node (ref "R70") (pin "2") (pinfunction "2_2") (pintype "input"))
    )
    (net (code "67") (name "Net-(Q8-G)") (class "Default")
      (node (ref "Q8") (pin "1") (pinfunction "G_1") (pintype "unspecified"))
      (node (ref "R71") (pin "2") (pinfunction "2_2") (pintype "input"))
    )
    (net (code "68") (name "Net-(Q9-B)") (class "Default")
      (node (ref "Q9") (pin "1") (pinfunction "B_1") (pintype "input"))
      (node (ref "R74") (pin "2") (pinfunction "2_2") (pintype "input"))
    )
    (net (code "69") (name "Net-(U1-G)") (class "Default")
      (node (ref "R23") (pin "2") (pinfunction "2_2") (pintype "input"))
      (node (ref "R30") (pin "1") (pinfunction "1_1") (pintype "input"))
      (node (ref "U1") (pin "1") (pinfunction "G_1") (pintype "unspecified"))
    )
    (net (code "70") (name "Net-(U3-CFG2)") (class "Default")
      (node (ref "C8") (pin "2") (pinfunction "2_2") (pintype "input"))
      (node (ref "R4") (pin "1") (pinfunction "1_1") (pintype "input"))
      (node (ref "U3") (pin "1") (pinfunction "VDD_1") (pintype "unspecified"))
      (node (ref "U3") (pin "2") (pinfunction "CFG2_2") (pintype "unspecified"))
    )
    (net (code "71") (name "Net-(U3-DM)") (class "Default")
      (node (ref "U3") (pin "4") (pinfunction "DP_4") (pintype "unspecified"))
      (node (ref "U3") (pin "5") (pinfunction "DM_5") (pintype "unspecified"))
    )
    (net (code "72") (name "Net-(U3-VBUS)") (class "Default")
      (node (ref "R3") (pin "2") (pinfunction "2_2") (pintype "input"))
      (node (ref "U3") (pin "8") (pinfunction "VBUS_8") (pintype "unspecified"))
    )
    (net (code "73") (name "Net-(U4-BOOT)") (class "Default")
      (node (ref "C12") (pin "1") (pinfunction "1_1") (pintype "input"))
      (node (ref "U4") (pin "1") (pinfunction "BOOT_1") (pintype "unspecified"))
    )
    (net (code "74") (name "Net-(U4-FB)") (class "Default")
      (node (ref "C13") (pin "1") (pinfunction "1_1") (pintype "input"))
      (node (ref "R5") (pin "2") (pinfunction "2_2") (pintype "input"))
      (node (ref "R6") (pin "1") (pinfunction "1_1") (pintype "input"))
      (node (ref "U4") (pin "3") (pinfunction "FB_3") (pintype "unspecified"))
    )
    (net (code "75") (name "Net-(U4-LX)") (class "Default")
      (node (ref "C12") (pin "2") (pinfunction "2_2") (pintype "input"))
      (node (ref "L1") (pin "1") (pinfunction "1_1") (pintype "unspecified"))
      (node (ref "U4") (pin "6") (pinfunction "LX_6") (pintype "unspecified"))
    )
    (net (code "76") (name "Net-(U5-BS)") (class "Default")
      (node (ref "C16") (pin "1") (pinfunction "1_1") (pintype "input"))
      (node (ref "U5") (pin "1") (pinfunction "BS_1") (pintype "unspecified"))
    )
    (net (code "77") (name "Net-(U5-FB)") (class "Default")
      (node (ref "C19") (pin "1") (pinfunction "1_1") (pintype "input"))
      (node (ref "R7") (pin "1") (pinfunction "1_1") (pintype "input"))
      (node (ref "R8") (pin "2") (pinfunction "2_2") (pintype "input"))
      (node (ref "U5") (pin "3") (pinfunction "FB_3") (pintype "unspecified"))
    )
    (net (code "78") (name "Net-(U5-LX)") (class "Default")
      (node (ref "C16") (pin "2") (pinfunction "2_2") (pintype "input"))
      (node (ref "L2") (pin "1") (pinfunction "1_1") (pintype "unspecified"))
      (node (ref "U5") (pin "6") (pinfunction "LX_6") (pintype "unspecified"))
    )
    (net (code "79") (name "Net-(U6-DITH)") (class "Default")
      (node (ref "C22") (pin "2") (pinfunction "2_2") (pintype "input"))
      (node (ref "U6") (pin "5") (pinfunction "DITH_5") (pintype "unspecified"))
    )
    (net (code "80") (name "Net-(U6-FB)") (class "Default")
      (node (ref "R12") (pin "1") (pinfunction "1_1") (pintype "input"))
      (node (ref "R13") (pin "2") (pinfunction "2_2") (pintype "input"))
      (node (ref "R14") (pin "2") (pinfunction "2_2") (pintype "input"))
      (node (ref "U6") (pin "11") (pinfunction "FB_11") (pintype "unspecified"))
    )
    (net (code "81") (name "Net-(U6-ISNS(+))") (class "Default")
      (node (ref "C26") (pin "2") (pinfunction "2_2") (pintype "input"))
      (node (ref "R16") (pin "2") (pinfunction "2_2") (pintype "input"))
      (node (ref "U6") (pin "14") (pinfunction "ISNS(+)_14") (pintype "unspecified"))
    )
    (net (code "82") (name "Net-(U6-ISNS(-))") (class "Default")
      (node (ref "C26") (pin "1") (pinfunction "1_1") (pintype "input"))
      (node (ref "R15") (pin "2") (pinfunction "2_2") (pintype "input"))
      (node (ref "U6") (pin "13") (pinfunction "ISNS(-)_13") (pintype "unspecified"))
    )
    (net (code "83") (name "Net-(U6-MODE)") (class "Default")
      (node (ref "R11") (pin "2") (pinfunction "2_2") (pintype "input"))
      (node (ref "U6") (pin "4") (pinfunction "MODE_4") (pintype "unspecified"))
    )
    (net (code "84") (name "Net-(U6-RT)") (class "Default")
      (node (ref "R10") (pin "2") (pinfunction "2_2") (pintype "input"))
      (node (ref "U6") (pin "6") (pinfunction "RT_6") (pintype "unspecified"))
    )
    (net (code "85") (name "Net-(U6-SLOPE)") (class "Default")
      (node (ref "C23") (pin "2") (pinfunction "2_2") (pintype "input"))
      (node (ref "U6") (pin "7") (pinfunction "SLOPE_7") (pintype "unspecified"))
    )
    (net (code "86") (name "Net-(U6-SS)") (class "Default")
      (node (ref "C24") (pin "2") (pinfunction "2_2") (pintype "input"))
      (node (ref "U6") (pin "8") (pinfunction "SS_8") (pintype "unspecified"))
    )
    (net (code "87") (name "Net-(U6-VIN)") (class "Default")
      (node (ref "C25") (pin "1") (pinfunction "1_1") (pintype "input"))
      (node (ref "R9") (pin "2") (pinfunction "2_2") (pintype "input"))
      (node (ref "U6") (pin "2") (pinfunction "VIN_2") (pintype "unspecified"))
    )
    (net (code "88") (name "Net-(U7-G)") (class "Default")
      (node (ref "R20") (pin "2") (pinfunction "2_2") (pintype "input"))
      (node (ref "R27") (pin "2") (pinfunction "2_2") (pintype "input"))
      (node (ref "U7") (pin "1") (pinfunction "G_1") (pintype "unspecified"))
    )
    (net (code "89") (name "Net-(U8-G)") (class "Default")
      (node (ref "R21") (pin "2") (pinfunction "2_2") (pintype "input"))
      (node (ref "R28") (pin "2") (pinfunction "2_2") (pintype "input"))
      (node (ref "U8") (pin "1") (pinfunction "G_1") (pintype "unspecified"))
    )
    (net (code "90") (name "Net-(U9-G)") (class "Default")
      (node (ref "R22") (pin "2") (pinfunction "2_2") (pintype "input"))
      (node (ref "R29") (pin "1") (pinfunction "1_1") (pintype "input"))
      (node (ref "U9") (pin "1") (pinfunction "G_1") (pintype "unspecified"))
    )
    (net (code "91") (name "Net-(U11A-+IN_2)") (class "Default")
      (node (ref "C56") (pin "2") (pinfunction "2_2") (pintype "input"))
      (node (ref "R42") (pin "2") (pinfunction "2_2") (pintype "input"))
      (node (ref "U11") (pin "5") (pinfunction "+IN_2_5") (pintype "unspecified"))
    )
    (net (code "92") (name "Net-(U11A--IN_2)") (class "Default")
      (node (ref "C57") (pin "1") (pinfunction "1_1") (pintype "input"))
      (node (ref "C58") (pin "1") (pinfunction "1_1") (pintype "input"))
      (node (ref "R41") (pin "2") (pinfunction "2_2") (pintype "input"))
      (node (ref "U11") (pin "6") (pinfunction "-IN_2_6") (pintype "unspecified"))
    )
    (net (code "93") (name "Net-(U11B-+IN_1)") (class "Default")
      (node (ref "R46") (pin "2") (pinfunction "2_2") (pintype "input"))
      (node (ref "R48") (pin "1") (pinfunction "1_1") (pintype "input"))
      (node (ref "U11") (pin "3") (pinfunction "+IN_1_3") (pintype "unspecified"))
    )
    (net (code "94") (name "Net-(U11B--IN_1)") (class "Default")
      (node (ref "R45") (pin "2") (pinfunction "2_2") (pintype "input"))
      (node (ref "R47") (pin "1") (pinfunction "1_1") (pintype "input"))
      (node (ref "U11") (pin "2") (pinfunction "-IN_1_2") (pintype "unspecified"))
    )
    (net (code "95") (name "Net-(U12-CATHODE)") (class "Default")
      (node (ref "R55") (pin "1") (pinfunction "1_1") (pintype "input"))
      (node (ref "U12") (pin "1") (pinfunction "CATHODE_1") (pintype "unspecified"))
    )
    (net (code "96") (name "Net-(U12-REF)") (class "Default")
      (node (ref "R53") (pin "1") (pinfunction "1_1") (pintype "input"))
      (node (ref "R54") (pin "2") (pinfunction "2_2") (pintype "input"))
      (node (ref "U12") (pin "2") (pinfunction "REF_2") (pintype "unspecified"))
    )
    (net (code "97") (name "Net-(U13-LNA_IN)") (class "Default")
      (node (ref "L5") (pin "2") (pinfunction "2_2") (pintype "unspecified"))
      (node (ref "U13") (pin "2") (pinfunction "LNA_IN_2") (pintype "unspecified"))
    )
    (net (code "98") (name "Net-(U16-VREFIN{slash}VREFOUT)") (class "Default")
      (node (ref "C74") (pin "2") (pinfunction "2_2") (pintype "input"))
      (node (ref "R66") (pin "1") (pinfunction "1_1") (pintype "input"))
      (node (ref "U16") (pin "10") (pinfunction "VREFIN/VREFOUT_10") (pintype "bidirectional"))
    )
    (net (code "99") (name "Net-(U18-G)") (class "Default")
      (node (ref "U18") (pin "1") (pinfunction "G_1") (pintype "unspecified"))
      (node (ref "U2") (pin "5") (pinfunction "GATE_5") (pintype "unspecified"))
    )
    (net (code "100") (name "PCNT_A") (class "Default")
      (node (ref "C76") (pin "1") (pinfunction "1_1") (pintype "input"))
      (node (ref "R68") (pin "2") (pinfunction "2_2") (pintype "input"))
      (node (ref "SW1") (pin "A") (pinfunction "A_A") (pintype "unspecified"))
      (node (ref "U13") (pin "39") (pinfunction "IO22_39") (pintype "unspecified"))
    )
    (net (code "101") (name "PCNT_B") (class "Default")
      (node (ref "C77") (pin "2") (pinfunction "2_2") (pintype "input"))
      (node (ref "R69") (pin "1") (pinfunction "1_1") (pintype "input"))
      (node (ref "SW1") (pin "B") (pinfunction "B_B") (pintype "unspecified"))
      (node (ref "U13") (pin "42") (pinfunction "IO21_42") (pintype "unspecified"))
    )
    (net (code "102") (name "PG") (class "Default")
      (node (ref "LED1") (pin "2") (pinfunction "A_2") (pintype "input"))
      (node (ref "R32") (pin "1") (pinfunction "1_1") (pintype "input"))
      (node (ref "U6") (pin "17") (pinfunction "PGOOD_17") (pintype "unspecified"))
    )
    (net (code "103") (name "PWMA") (class "Default")
      (node (ref "C70") (pin "1") (pinfunction "1_1") (pintype "input"))
      (node (ref "U13") (pin "13") (pinfunction "IO33_13") (pintype "unspecified"))
    )
    (net (code "104") (name "PWMB") (class "Default")
      (node (ref "C72") (pin "1") (pinfunction "1_1") (pintype "input"))
      (node (ref "U13") (pin "12") (pinfunction "IO32_12") (pintype "unspecified"))
    )
    (net (code "105") (name "PWR_IN") (class "Default")
      (node (ref "C67") (pin "2") (pinfunction "2_2") (pintype "input"))
      (node (ref "R64") (pin "1") (pinfunction "1_1") (pintype "input"))
      (node (ref "R65") (pin "1") (pinfunction "1_1") (pintype "input"))
      (node (ref "U13") (pin "10") (pinfunction "IO34_10") (pintype "unspecified"))
    )
    (net (code "106") (name "RTS") (class "Default")
      (node (ref "Q6") (pin "1") (pinfunction "E_1") (pintype "unspecified"))
      (node (ref "R63") (pin "1") (pinfunction "1_1") (pintype "input"))
      (node (ref "U14") (pin "14") (pinfunction "RTS#_14") (pintype "unspecified"))
    )
    (net (code "107") (name "RXD") (class "Default")
      (node (ref "U13") (pin "41") (pinfunction "U0TXD_41") (pintype "unspecified"))
      (node (ref "U14") (pin "3") (pinfunction "RXD_3") (pintype "unspecified"))
    )
    (net (code "108") (name "SCLK") (class "Default")
      (node (ref "FPC1") (pin "3") (pinfunction "3_3") (pintype "unspecified"))
      (node (ref "U13") (pin "35") (pinfunction "IO18_35") (pintype "unspecified"))
      (node (ref "U16") (pin "7") (pinfunction "SCLK_7") (pintype "unspecified"))
    )
    (net (code "109") (name "SW1") (class "Default")
      (node (ref "C30") (pin "1") (pinfunction "1_1") (pintype "input"))
      (node (ref "C33") (pin "2") (pinfunction "2_2") (pintype "input"))
      (node (ref "D5") (pin "1") (pinfunction "K_1") (pintype "unspecified"))
      (node (ref "L3") (pin "1") (pinfunction "1_1") (pintype "unspecified"))
      (node (ref "R20") (pin "1") (pinfunction "1_1") (pintype "input"))
      (node (ref "U6") (pin "28") (pinfunction "SW1_28") (pintype "unspecified"))
      (node (ref "U7") (pin "3") (pinfunction "S_3") (pintype "unspecified"))
      (node (ref "U8") (pin "2") (pinfunction "D_2") (pintype "unspecified"))
    )
    (net (code "110") (name "SW2") (class "Default")
      (node (ref "C31") (pin "1") (pinfunction "1_1") (pintype "input"))
      (node (ref "C34") (pin "2") (pinfunction "2_2") (pintype "input"))
      (node (ref "L3") (pin "2") (pinfunction "2_2") (pintype "unspecified"))
      (node (ref "R22") (pin "1") (pinfunction "1_1") (pintype "input"))
      (node (ref "U1") (pin "2") (pinfunction "D_2") (pintype "unspecified"))
      (node (ref "U6") (pin "18") (pinfunction "SW2_18") (pintype "unspecified"))
      (node (ref "U9") (pin "3") (pinfunction "S_3") (pintype "unspecified"))
    )
    (net (code "111") (name "TEMP") (class "Default")
      (node (ref "C79") (pin "2") (pinfunction "2_2") (pintype "input"))
      (node (ref "R72") (pin "2") (pinfunction "2_2") (pintype "input"))
      (node (ref "R73") (pin "1") (pinfunction "1_1") (pintype "input"))
      (node (ref "U13") (pin "5") (pinfunction "SENSOR_VP_5") (pintype "unspecified"))
    )
    (net (code "112") (name "TXD") (class "Default")
      (node (ref "U13") (pin "40") (pinfunction "U0RXD_40") (pintype "unspecified"))
      (node (ref "U14") (pin "2") (pinfunction "TXD_2") (pintype "unspecified"))
    )
    (net (code "113") (name "USB_N") (class "Default")
      (node (ref "U14") (pin "6") (pinfunction "D-_6") (pintype "unspecified"))
      (node (ref "USB1") (pin "A7") (pinfunction "DN1_A7") (pintype "unspecified"))
      (node (ref "USB1") (pin "B7") (pinfunction "DN2_B7") (pintype "unspecified"))
    )
    (net (code "114") (name "USB_P") (class "Default")
      (node (ref "U14") (pin "5") (pinfunction "D+_5") (pintype "unspecified"))
      (node (ref "USB1") (pin "A6") (pinfunction "DP1_A6") (pintype "unspecified"))
      (node (ref "USB1") (pin "B6") (pinfunction "DP2_B6") (pintype "unspecified"))
    )
    (net (code "115") (name "USET") (class "Default")
      (node (ref "R13") (pin "1") (pinfunction "1_1") (pintype "input"))
      (node (ref "U16") (pin "1") (pinfunction "VOUTA_1") (pintype "output"))
    )
    (net (code "116") (name "VBUS") (class "Default")
      (node (ref "C6") (pin "2") (pinfunction "2_2") (pintype "input"))
      (node (ref "D3") (pin "2") (pinfunction "A_2") (pintype "unspecified"))
      (node (ref "R3") (pin "1") (pinfunction "1_1") (pintype "input"))
      (node (ref "R4") (pin "2") (pinfunction "2_2") (pintype "input"))
      (node (ref "U18") (pin "3") (pinfunction "S_3") (pintype "unspecified"))
      (node (ref "U2") (pin "4") (pinfunction "IN_4") (pintype "unspecified"))
      (node (ref "USB1") (pin "A4") (pinfunction "VBUS_A4") (pintype "unspecified"))
      (node (ref "USB1") (pin "A9") (pinfunction "VBUS_A9") (pintype "unspecified"))
      (node (ref "USB1") (pin "B4") (pinfunction "VBUS_B4") (pintype "unspecified"))
      (node (ref "USB1") (pin "B9") (pinfunction "VBUS_B9") (pintype "unspecified"))
    )
    (net (code "117") (name "VCC") (class "Default")
      (node (ref "C32") (pin "1") (pinfunction "1_1") (pintype "input"))
      (node (ref "D23") (pin "2") (pinfunction "A_2") (pintype "unspecified"))
      (node (ref "D24") (pin "2") (pinfunction "A_2") (pintype "unspecified"))
      (node (ref "R32") (pin "2") (pinfunction "2_2") (pintype "input"))
      (node (ref "U6") (pin "23") (pinfunction "VCC_23") (pintype "unspecified"))
    )
    (net (code "118") (name "VIN") (class "Default")
      (node (ref "C1") (pin "2") (pinfunction "2_2") (pintype "input"))
      (node (ref "C10") (pin "2") (pinfunction "2_2") (pintype "input"))
      (node (ref "C11") (pin "2") (pinfunction "2_2") (pintype "input"))
      (node (ref "C3") (pin "2") (pinfunction "2_2") (pintype "input"))
      (node (ref "C36") (pin "2") (pinfunction "2_2") (pintype "input"))
      (node (ref "C37") (pin "2") (pinfunction "2_2") (pintype "input"))
      (node (ref "C7") (pin "2") (pinfunction "2_2") (pintype "unspecified"))
      (node (ref "C81") (pin "1") (pinfunction "1_1") (pintype "input"))
      (node (ref "CN1") (pin "2") (pinfunction "+_2") (pintype "unspecified"))
      (node (ref "D1") (pin "2") (pinfunction "A_2") (pintype "input"))
      (node (ref "D25") (pin "2") (pinfunction "A_2") (pintype "unspecified"))
      (node (ref "P1") (pin "2") (pinfunction "2_2") (pintype "unspecified"))
      (node (ref "R1") (pin "2") (pinfunction "2_2") (pintype "input"))
      (node (ref "R64") (pin "2") (pinfunction "2_2") (pintype "input"))
      (node (ref "U18") (pin "2") (pinfunction "D_2") (pintype "unspecified"))
      (node (ref "U2") (pin "1") (pinfunction "VS_1") (pintype "unspecified"))
      (node (ref "U2") (pin "6") (pinfunction "OUT_6") (pintype "unspecified"))
      (node (ref "U4") (pin "4") (pinfunction "EN_4") (pintype "unspecified"))
      (node (ref "U4") (pin "5") (pinfunction "VIN_5") (pintype "unspecified"))
      (node (ref "U6") (pin "3") (pinfunction "VISNS_3") (pintype "unspecified"))
      (node (ref "U7") (pin "2") (pinfunction "D_2") (pintype "unspecified"))
    )
    (net (code "119") (name "VO") (class "Default")
      (node (ref "C38") (pin "1") (pinfunction "1_1") (pintype "input"))
      (node (ref "C40") (pin "2") (pinfunction "2_2") (pintype "input"))
      (node (ref "C41") (pin "2") (pinfunction "2_2") (pintype "input"))
      (node (ref "C42") (pin "2") (pinfunction "2_2") (pintype "input"))
      (node (ref "C49") (pin "2") (pinfunction "2_2") (pintype "input"))
      (node (ref "C50") (pin "2") (pinfunction "2_2") (pintype "input"))
      (node (ref "L6") (pin "1") (pinfunction "1_1") (pintype "input"))
      (node (ref "R35") (pin "2") (pinfunction "2_2") (pintype "input"))
      (node (ref "U9") (pin "2") (pinfunction "D_2") (pintype "unspecified"))
    )
    (net (code "120") (name "VOS") (class "Default")
      (node (ref "R12") (pin "2") (pinfunction "2_2") (pintype "input"))
      (node (ref "R48") (pin "2") (pinfunction "2_2") (pintype "input"))
      (node (ref "U11") (pin "1") (pinfunction "OUT_1_1") (pintype "output"))
      (node (ref "U13") (pin "8") (pinfunction "SENSOR_VN_8") (pintype "unspecified"))
    )
    (net (code "121") (name "VOUT") (class "Default")
      (node (ref "C45") (pin "2") (pinfunction "2_2") (pintype "input"))
      (node (ref "C47") (pin "2") (pinfunction "2_2") (pintype "input"))
      (node (ref "C48") (pin "2") (pinfunction "2_2") (pintype "input"))
      (node (ref "C52") (pin "2") (pinfunction "2_2") (pintype "input"))
      (node (ref "C53") (pin "2") (pinfunction "2_2") (pintype "input"))
      (node (ref "CN2") (pin "4") (pinfunction "4_4") (pintype "unspecified"))
      (node (ref "D10") (pin "2") (pinfunction "A_2") (pintype "unspecified"))
      (node (ref "D7") (pin "2") (pinfunction "2_2") (pintype "unspecified"))
      (node (ref "D9") (pin "1") (pinfunction "K_1") (pintype "unspecified"))
      (node (ref "R15") (pin "1") (pinfunction "1_1") (pintype "input"))
      (node (ref "R36") (pin "2") (pinfunction "2_2") (pintype "unspecified"))
      (node (ref "R37") (pin "2") (pinfunction "2_2") (pintype "unspecified"))
      (node (ref "R38") (pin "2") (pinfunction "2_2") (pintype "unspecified"))
      (node (ref "R40") (pin "1") (pinfunction "1_1") (pintype "input"))
      (node (ref "R49") (pin "1") (pinfunction "1_1") (pintype "input"))
      (node (ref "R53") (pin "2") (pinfunction "2_2") (pintype "input"))
    )
    (net (code "122") (name "VOUTP") (class "Default")
      (node (ref "C39") (pin "1") (pinfunction "1_1") (pintype "input"))
      (node (ref "C43") (pin "2") (pinfunction "2_2") (pintype "input"))
      (node (ref "C44") (pin "2") (pinfunction "2_2") (pintype "input"))
      (node (ref "L6") (pin "2") (pinfunction "2_2") (pintype "input"))
      (node (ref "R16") (pin "1") (pinfunction "1_1") (pintype "input"))
      (node (ref "R36") (pin "1") (pinfunction "1_1") (pintype "unspecified"))
      (node (ref "R37") (pin "1") (pinfunction "1_1") (pintype "unspecified"))
      (node (ref "R38") (pin "1") (pinfunction "1_1") (pintype "unspecified"))
      (node (ref "R39") (pin "1") (pinfunction "1_1") (pintype "input"))
      (node (ref "U6") (pin "12") (pinfunction "VOSNS_12") (pintype "unspecified"))
    )
    (net (code "123") (name "VREF") (class "Default")
      (node (ref "C69") (pin "2") (pinfunction "2_2") (pintype "input"))
      (node (ref "R66") (pin "2") (pinfunction "2_2") (pintype "input"))
      (node (ref "U15") (pin "2") (pinfunction "OUT_2") (pintype "unspecified"))
    )
    (net (code "124") (name "unconnected-(CN1-Pad3)") (class "Default")
      (node (ref "CN1") (pin "3") (pinfunction "3_3") (pintype "unspecified"))
    )
    (net (code "125") (name "unconnected-(CN1-Pad4)") (class "Default")
      (node (ref "CN1") (pin "4") (pinfunction "4_4") (pintype "unspecified"))
    )
    (net (code "126") (name "unconnected-(FPC1-Pad7)") (class "Default")
      (node (ref "FPC1") (pin "7") (pinfunction "7_7") (pintype "unspecified+no_connect"))
    )
    (net (code "127") (name "unconnected-(L3-Pad3)") (class "Default")
      (node (ref "L3") (pin "3") (pinfunction "3_3") (pintype "unspecified"))
    )
    (net (code "128") (name "unconnected-(L5-ANT-Pad1)") (class "Default")
      (node (ref "L5") (pin "1") (pinfunction "ANT_1") (pintype "unspecified"))
    )
    (net (code "129") (name "unconnected-(U3-PG-Pad10)") (class "Default")
      (node (ref "U3") (pin "10") (pinfunction "PG_10") (pintype "unspecified+no_connect"))
    )
    (net (code "130") (name "unconnected-(U10-NC-Pad1)") (class "Default")
      (node (ref "U10") (pin "1") (pinfunction "NC_1") (pintype "unspecified"))
    )
    (net (code "131") (name "unconnected-(U13-CAP1_NC-Pad48)") (class "Default")
      (node (ref "U13") (pin "48") (pinfunction "CAP1_NC_48") (pintype "unspecified+no_connect"))
    )
    (net (code "132") (name "unconnected-(U13-CAP2_NC-Pad47)") (class "Default")
      (node (ref "U13") (pin "47") (pinfunction "CAP2_NC_47") (pintype "unspecified+no_connect"))
    )
    (net (code "133") (name "unconnected-(U13-CLK-Pad31)") (class "Default")
      (node (ref "U13") (pin "31") (pinfunction "CLK_31") (pintype "unspecified+no_connect"))
    )
    (net (code "134") (name "unconnected-(U13-CMD-Pad30)") (class "Default")
      (node (ref "U13") (pin "30") (pinfunction "CMD_30") (pintype "unspecified+no_connect"))
    )
    (net (code "135") (name "unconnected-(U13-IO2-Pad22)") (class "Default")
      (node (ref "U13") (pin "22") (pinfunction "IO2_22") (pintype "unspecified"))
    )
    (net (code "136") (name "unconnected-(U13-IO16-Pad25)") (class "Default")
      (node (ref "U13") (pin "25") (pinfunction "IO16_25") (pintype "unspecified+no_connect"))
    )
    (net (code "137") (name "unconnected-(U13-IO17-Pad27)") (class "Default")
      (node (ref "U13") (pin "27") (pinfunction "IO17_27") (pintype "unspecified+no_connect"))
    )
    (net (code "138") (name "unconnected-(U13-IO27-Pad16)") (class "Default")
      (node (ref "U13") (pin "16") (pinfunction "IO27_16") (pintype "unspecified"))
    )
    (net (code "139") (name "unconnected-(U13-SD0-Pad32)") (class "Default")
      (node (ref "U13") (pin "32") (pinfunction "SD0_32") (pintype "unspecified+no_connect"))
    )
    (net (code "140") (name "unconnected-(U13-SD1-Pad33)") (class "Default")
      (node (ref "U13") (pin "33") (pinfunction "SD1_33") (pintype "unspecified+no_connect"))
    )
    (net (code "141") (name "unconnected-(U13-VDD_SDIO-Pad26)") (class "Default")
      (node (ref "U13") (pin "26") (pinfunction "VDD_SDIO_26") (pintype "unspecified+no_connect"))
    )
    (net (code "142") (name "unconnected-(U13-XTAL_N_NC-Pad44)") (class "Default")
      (node (ref "U13") (pin "44") (pinfunction "XTAL_N_NC_44") (pintype "unspecified+no_connect"))
    )
    (net (code "143") (name "unconnected-(U13-XTAL_P_NC-Pad45)") (class "Default")
      (node (ref "U13") (pin "45") (pinfunction "XTAL_P_NC_45") (pintype "unspecified+no_connect"))
    )
    (net (code "144") (name "unconnected-(U14-CTS#-Pad9)") (class "Default")
      (node (ref "U14") (pin "9") (pinfunction "CTS#_9") (pintype "unspecified+no_connect"))
    )
    (net (code "145") (name "unconnected-(U14-DCD#-Pad12)") (class "Default")
      (node (ref "U14") (pin "12") (pinfunction "DCD#_12") (pintype "unspecified+no_connect"))
    )
    (net (code "146") (name "unconnected-(U14-DSR#-Pad10)") (class "Default")
      (node (ref "U14") (pin "10") (pinfunction "DSR#_10") (pintype "unspecified+no_connect"))
    )
    (net (code "147") (name "unconnected-(U14-NC.-Pad7)") (class "Default")
      (node (ref "U14") (pin "7") (pinfunction "NC._7") (pintype "unspecified+no_connect"))
    )
    (net (code "148") (name "unconnected-(U14-OUT#-Pad8)") (class "Default")
      (node (ref "U14") (pin "8") (pinfunction "OUT#_8") (pintype "unspecified+no_connect"))
    )
    (net (code "149") (name "unconnected-(U14-R232-Pad15)") (class "Default")
      (node (ref "U14") (pin "15") (pinfunction "R232_15") (pintype "unspecified+no_connect"))
    )
    (net (code "150") (name "unconnected-(U14-RI#-Pad11)") (class "Default")
      (node (ref "U14") (pin "11") (pinfunction "RI#_11") (pintype "unspecified+no_connect"))
    )
    (net (code "151") (name "unconnected-(USB1-SUB1-PadA8)") (class "Default")
      (node (ref "USB1") (pin "A8") (pinfunction "SUB1_A8") (pintype "unspecified+no_connect"))
    )
    (net (code "152") (name "unconnected-(USB1-SUB2-PadB8)") (class "Default")
      (node (ref "USB1") (pin "B8") (pinfunction "SUB2_B8") (pintype "unspecified+no_connect"))
    )
  )
)
